# Sheet1.net
KiCad netlist of a schematic drawn in Altium Designer
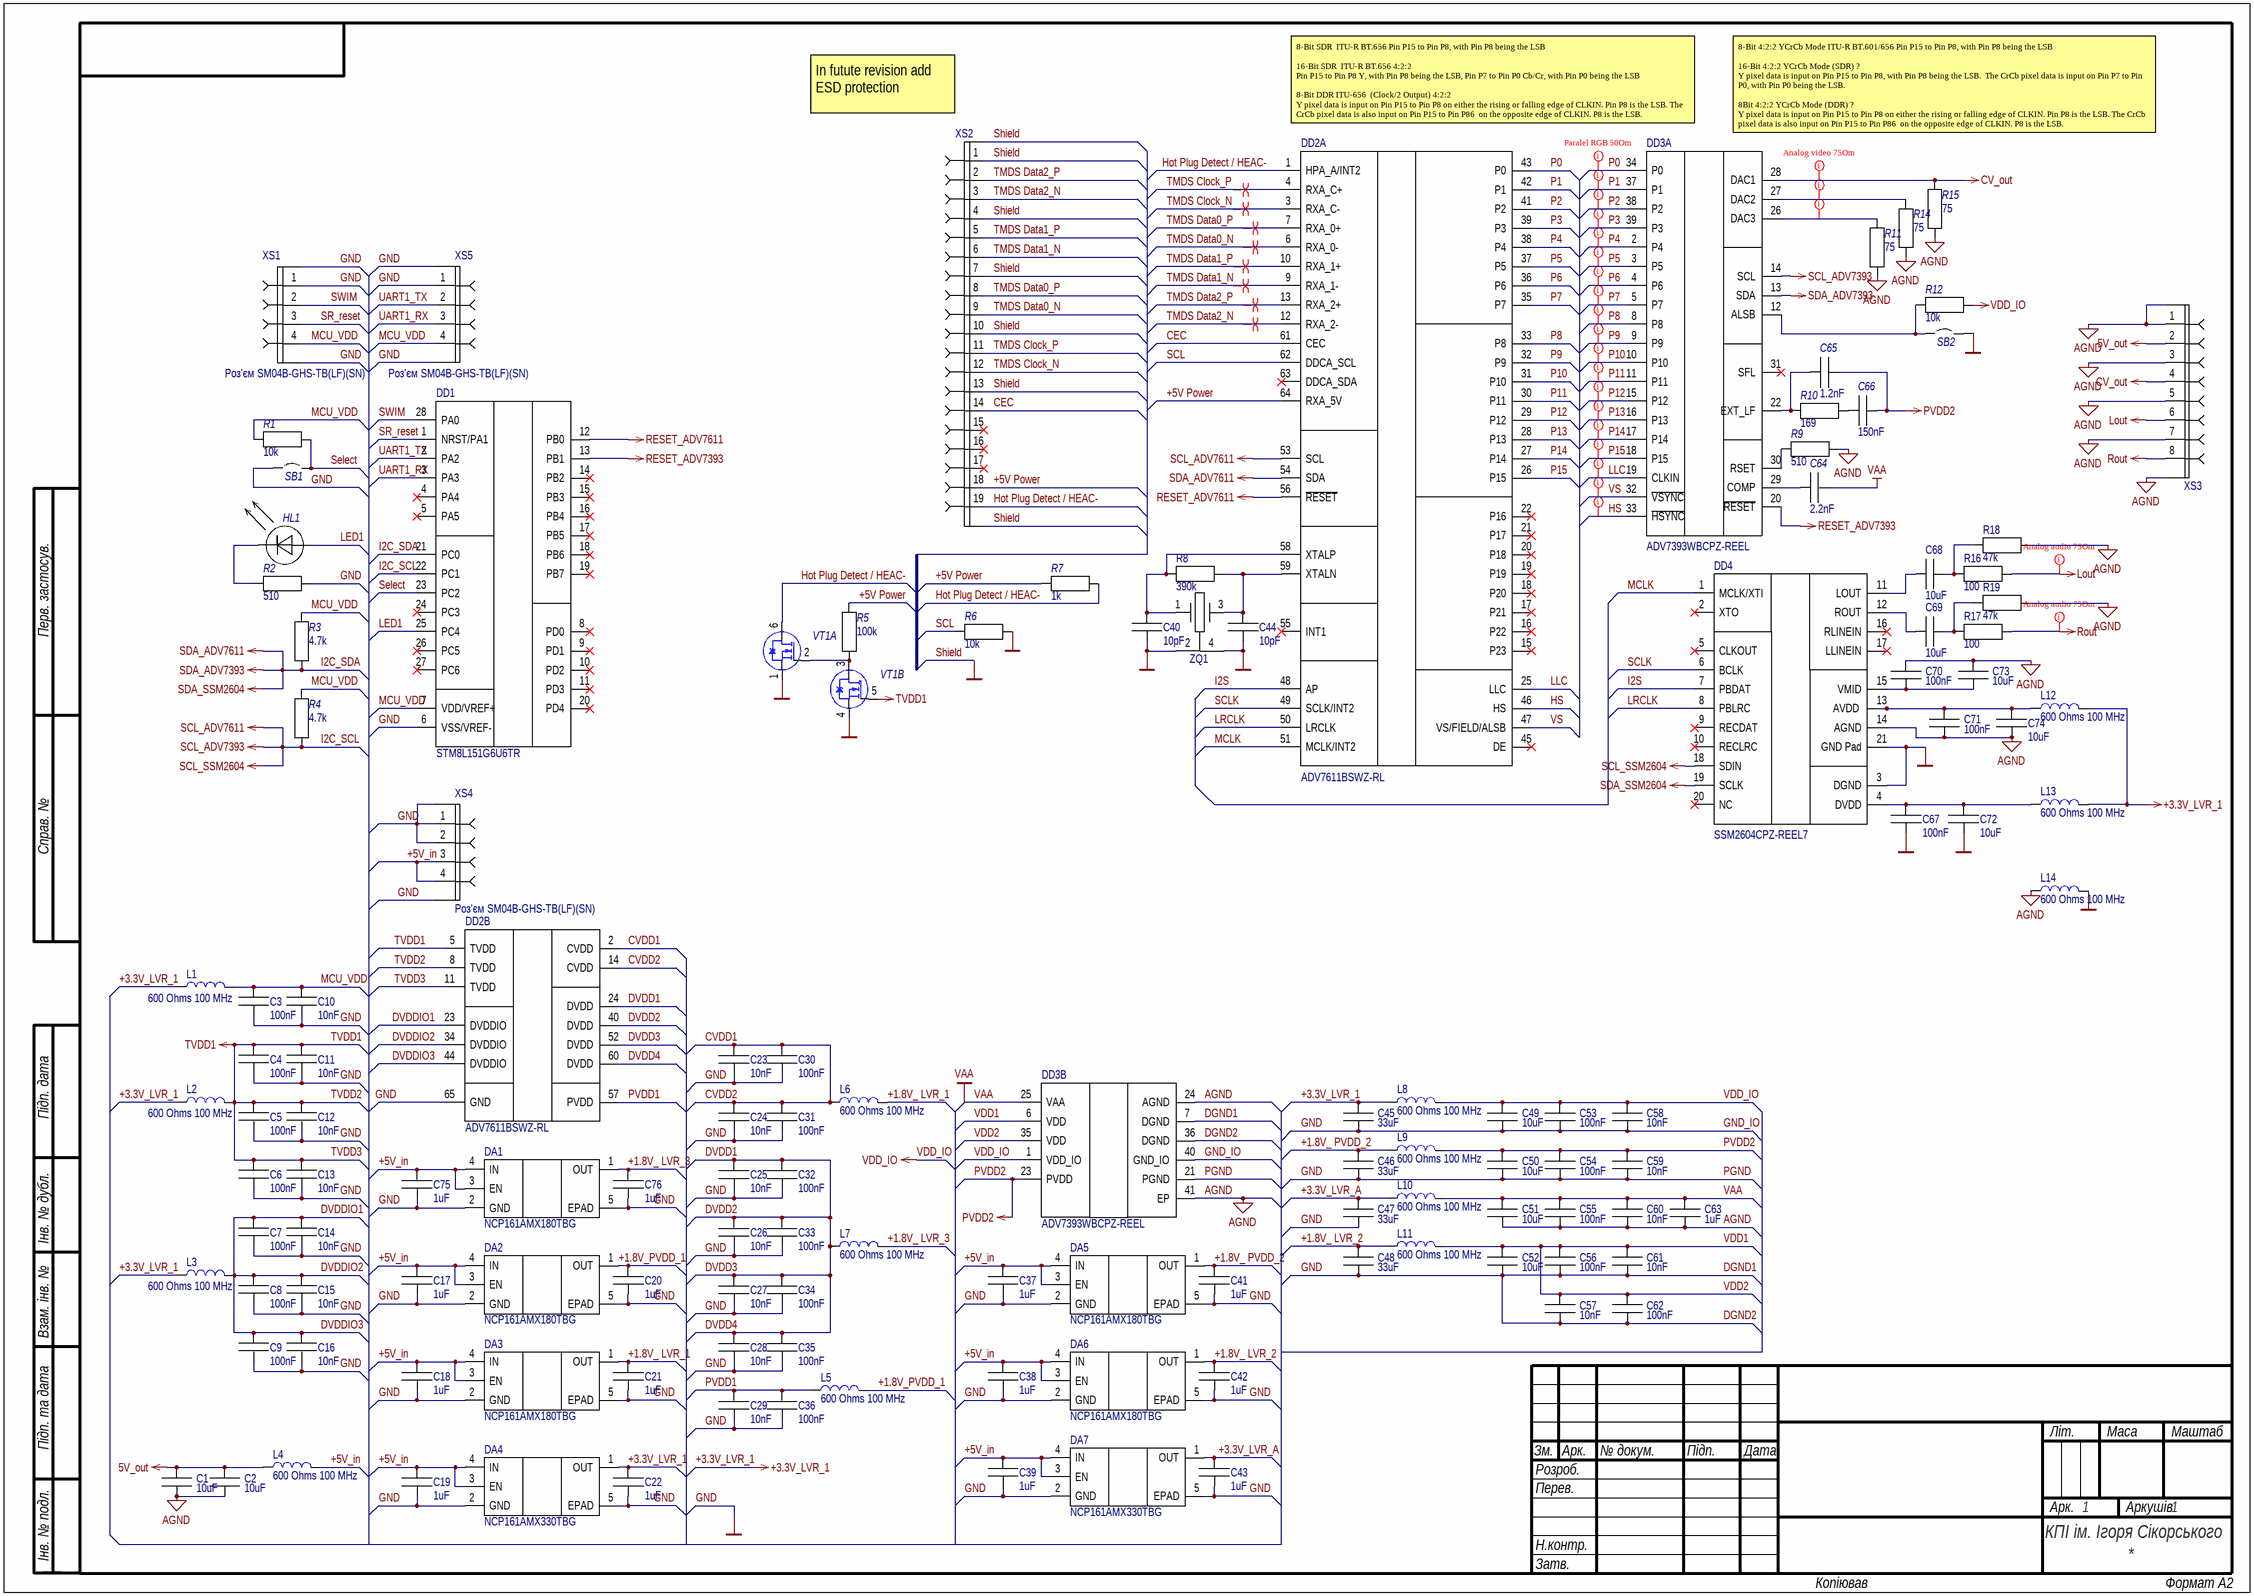
[diagram p0: Sheet1.SchDoc]

(export (version "E")
  (design (tool "Eeschema 10.0.6"))
  (components
    (comp (ref "C1")
      (value "10uF")
      (footprint "SC0603_L")
      (description "10 µF ±20% 6.3V Ceramic Capacitor X5R 0603 (1608 Metric)")
      (fields (field (name "Comment") "CL10A106MQ8NNNC"))
      (libsource (lib "Schlib2") (part "C0603-10µF-6.3V-10CL10A106MQ8NNNC"))
    )
    (comp (ref "C2")
      (value "10uF")
      (footprint "SC0603_L")
      (description "10 µF ±20% 6.3V Ceramic Capacitor X5R 0603 (1608 Metric)")
      (fields (field (name "Comment") "CL10A106MQ8NNNC"))
      (libsource (lib "Schlib2") (part "C0603-10µF-6.3V-10CL10A106MQ8NNNC"))
    )
    (comp (ref "C3")
      (value "100nF")
      (footprint "FP-C0402-BB-IPC_A")
      (description "0.1 µF ±10% 16V Ceramic Capacitor X7R 0402 (1005 Metric)")
      (fields (field (name "Comment") "C0402C104K4RAC7867"))
      (libsource (lib "Schlib2") (part "C0402-100nF-16V-C0402C104K4RAC7867"))
    )
    (comp (ref "C4")
      (value "100nF")
      (footprint "FP-C0402-BB-IPC_A")
      (description "0.1 µF ±10% 16V Ceramic Capacitor X7R 0402 (1005 Metric)")
      (fields (field (name "Comment") "C0402C104K4RAC7867"))
      (libsource (lib "Schlib2") (part "C0402-100nF-16V-C0402C104K4RAC7867"))
    )
    (comp (ref "C5")
      (value "100nF")
      (footprint "FP-C0402-BB-IPC_A")
      (description "0.1 µF ±10% 16V Ceramic Capacitor X7R 0402 (1005 Metric)")
      (fields (field (name "Comment") "C0402C104K4RAC7867"))
      (libsource (lib "Schlib2") (part "C0402-100nF-16V-C0402C104K4RAC7867"))
    )
    (comp (ref "C6")
      (value "100nF")
      (footprint "FP-C0402-BB-IPC_A")
      (description "0.1 µF ±10% 16V Ceramic Capacitor X7R 0402 (1005 Metric)")
      (fields (field (name "Comment") "C0402C104K4RAC7867"))
      (libsource (lib "Schlib2") (part "C0402-100nF-16V-C0402C104K4RAC7867"))
    )
    (comp (ref "C7")
      (value "100nF")
      (footprint "FP-C0402-BB-IPC_A")
      (description "0.1 µF ±10% 16V Ceramic Capacitor X7R 0402 (1005 Metric)")
      (fields (field (name "Comment") "C0402C104K4RAC7867"))
      (libsource (lib "Schlib2") (part "C0402-100nF-16V-C0402C104K4RAC7867"))
    )
    (comp (ref "C8")
      (value "100nF")
      (footprint "FP-C0402-BB-IPC_A")
      (description "0.1 µF ±10% 16V Ceramic Capacitor X7R 0402 (1005 Metric)")
      (fields (field (name "Comment") "C0402C104K4RAC7867"))
      (libsource (lib "Schlib2") (part "C0402-100nF-16V-C0402C104K4RAC7867"))
    )
    (comp (ref "C9")
      (value "100nF")
      (footprint "FP-C0402-BB-IPC_A")
      (description "0.1 µF ±10% 16V Ceramic Capacitor X7R 0402 (1005 Metric)")
      (fields (field (name "Comment") "C0402C104K4RAC7867"))
      (libsource (lib "Schlib2") (part "C0402-100nF-16V-C0402C104K4RAC7867"))
    )
    (comp (ref "C10")
      (value "10nF")
      (footprint "FP-C0402-BB-IPC_A")
      (description "10000 pF ±10% 16V Ceramic Capacitor X7R 0402 (1005 Metric)")
      (fields (field (name "Comment") "C0402C103K4RAC7867"))
      (libsource (lib "Schlib2") (part "C0402-10nF-16V-C0402C103K4RAC7867"))
    )
    (comp (ref "C11")
      (value "10nF")
      (footprint "FP-C0402-BB-IPC_A")
      (description "10000 pF ±10% 16V Ceramic Capacitor X7R 0402 (1005 Metric)")
      (fields (field (name "Comment") "C0402C103K4RAC7867"))
      (libsource (lib "Schlib2") (part "C0402-10nF-16V-C0402C103K4RAC7867"))
    )
    (comp (ref "C12")
      (value "10nF")
      (footprint "FP-C0402-BB-IPC_A")
      (description "10000 pF ±10% 16V Ceramic Capacitor X7R 0402 (1005 Metric)")
      (fields (field (name "Comment") "C0402C103K4RAC7867"))
      (libsource (lib "Schlib2") (part "C0402-10nF-16V-C0402C103K4RAC7867"))
    )
    (comp (ref "C13")
      (value "10nF")
      (footprint "FP-C0402-BB-IPC_A")
      (description "10000 pF ±10% 16V Ceramic Capacitor X7R 0402 (1005 Metric)")
      (fields (field (name "Comment") "C0402C103K4RAC7867"))
      (libsource (lib "Schlib2") (part "C0402-10nF-16V-C0402C103K4RAC7867"))
    )
    (comp (ref "C14")
      (value "10nF")
      (footprint "FP-C0402-BB-IPC_A")
      (description "10000 pF ±10% 16V Ceramic Capacitor X7R 0402 (1005 Metric)")
      (fields (field (name "Comment") "C0402C103K4RAC7867"))
      (libsource (lib "Schlib2") (part "C0402-10nF-16V-C0402C103K4RAC7867"))
    )
    (comp (ref "C15")
      (value "10nF")
      (footprint "FP-C0402-BB-IPC_A")
      (description "10000 pF ±10% 16V Ceramic Capacitor X7R 0402 (1005 Metric)")
      (fields (field (name "Comment") "C0402C103K4RAC7867"))
      (libsource (lib "Schlib2") (part "C0402-10nF-16V-C0402C103K4RAC7867"))
    )
    (comp (ref "C16")
      (value "10nF")
      (footprint "FP-C0402-BB-IPC_A")
      (description "10000 pF ±10% 16V Ceramic Capacitor X7R 0402 (1005 Metric)")
      (fields (field (name "Comment") "C0402C103K4RAC7867"))
      (libsource (lib "Schlib2") (part "C0402-10nF-16V-C0402C103K4RAC7867"))
    )
    (comp (ref "C17")
      (value "1uF")
      (footprint "SC0603_L")
      (description "1 µF ±10% 25V Ceramic Capacitor X5R 0603 (1608 Metric)")
      (fields (field (name "Comment") "CC0603KRX5R8BB105"))
      (libsource (lib "Schlib2") (part "C0603-1µF-25V-CC0603KRX5R8BB105"))
    )
    (comp (ref "C18")
      (value "1uF")
      (footprint "SC0603_L")
      (description "1 µF ±10% 25V Ceramic Capacitor X5R 0603 (1608 Metric)")
      (fields (field (name "Comment") "CC0603KRX5R8BB105"))
      (libsource (lib "Schlib2") (part "C0603-1µF-25V-CC0603KRX5R8BB105"))
    )
    (comp (ref "C19")
      (value "1uF")
      (footprint "SC0603_L")
      (description "1 µF ±10% 25V Ceramic Capacitor X5R 0603 (1608 Metric)")
      (fields (field (name "Comment") "CC0603KRX5R8BB105"))
      (libsource (lib "Schlib2") (part "C0603-1µF-25V-CC0603KRX5R8BB105"))
    )
    (comp (ref "C20")
      (value "1uF")
      (footprint "SC0603_L")
      (description "1 µF ±10% 25V Ceramic Capacitor X5R 0603 (1608 Metric)")
      (fields (field (name "Comment") "CC0603KRX5R8BB105"))
      (libsource (lib "Schlib2") (part "C0603-1µF-25V-CC0603KRX5R8BB105"))
    )
    (comp (ref "C21")
      (value "1uF")
      (footprint "SC0603_L")
      (description "1 µF ±10% 25V Ceramic Capacitor X5R 0603 (1608 Metric)")
      (fields (field (name "Comment") "CC0603KRX5R8BB105"))
      (libsource (lib "Schlib2") (part "C0603-1µF-25V-CC0603KRX5R8BB105"))
    )
    (comp (ref "C22")
      (value "1uF")
      (footprint "SC0603_L")
      (description "1 µF ±10% 25V Ceramic Capacitor X5R 0603 (1608 Metric)")
      (fields (field (name "Comment") "CC0603KRX5R8BB105"))
      (libsource (lib "Schlib2") (part "C0603-1µF-25V-CC0603KRX5R8BB105"))
    )
    (comp (ref "C23")
      (value "10nF")
      (footprint "FP-C0402-BB-IPC_A")
      (description "10000 pF ±10% 16V Ceramic Capacitor X7R 0402 (1005 Metric)")
      (fields (field (name "Comment") "C0402C103K4RAC7867"))
      (libsource (lib "Schlib2") (part "C0402-10nF-16V-C0402C103K4RAC7867"))
    )
    (comp (ref "C24")
      (value "10nF")
      (footprint "FP-C0402-BB-IPC_A")
      (description "10000 pF ±10% 16V Ceramic Capacitor X7R 0402 (1005 Metric)")
      (fields (field (name "Comment") "C0402C103K4RAC7867"))
      (libsource (lib "Schlib2") (part "C0402-10nF-16V-C0402C103K4RAC7867"))
    )
    (comp (ref "C25")
      (value "10nF")
      (footprint "FP-C0402-BB-IPC_A")
      (description "10000 pF ±10% 16V Ceramic Capacitor X7R 0402 (1005 Metric)")
      (fields (field (name "Comment") "C0402C103K4RAC7867"))
      (libsource (lib "Schlib2") (part "C0402-10nF-16V-C0402C103K4RAC7867"))
    )
    (comp (ref "C26")
      (value "10nF")
      (footprint "FP-C0402-BB-IPC_A")
      (description "10000 pF ±10% 16V Ceramic Capacitor X7R 0402 (1005 Metric)")
      (fields (field (name "Comment") "C0402C103K4RAC7867"))
      (libsource (lib "Schlib2") (part "C0402-10nF-16V-C0402C103K4RAC7867"))
    )
    (comp (ref "C27")
      (value "10nF")
      (footprint "FP-C0402-BB-IPC_A")
      (description "10000 pF ±10% 16V Ceramic Capacitor X7R 0402 (1005 Metric)")
      (fields (field (name "Comment") "C0402C103K4RAC7867"))
      (libsource (lib "Schlib2") (part "C0402-10nF-16V-C0402C103K4RAC7867"))
    )
    (comp (ref "C28")
      (value "10nF")
      (footprint "FP-C0402-BB-IPC_A")
      (description "10000 pF ±10% 16V Ceramic Capacitor X7R 0402 (1005 Metric)")
      (fields (field (name "Comment") "C0402C103K4RAC7867"))
      (libsource (lib "Schlib2") (part "C0402-10nF-16V-C0402C103K4RAC7867"))
    )
    (comp (ref "C29")
      (value "10nF")
      (footprint "FP-C0402-BB-IPC_A")
      (description "10000 pF ±10% 16V Ceramic Capacitor X7R 0402 (1005 Metric)")
      (fields (field (name "Comment") "C0402C103K4RAC7867"))
      (libsource (lib "Schlib2") (part "C0402-10nF-16V-C0402C103K4RAC7867"))
    )
    (comp (ref "C30")
      (value "100nF")
      (footprint "FP-C0402-BB-IPC_A")
      (description "0.1 µF ±10% 16V Ceramic Capacitor X7R 0402 (1005 Metric)")
      (fields (field (name "Comment") "C0402C104K4RAC7867"))
      (libsource (lib "Schlib2") (part "C0402-100nF-16V-C0402C104K4RAC7867"))
    )
    (comp (ref "C31")
      (value "100nF")
      (footprint "FP-C0402-BB-IPC_A")
      (description "0.1 µF ±10% 16V Ceramic Capacitor X7R 0402 (1005 Metric)")
      (fields (field (name "Comment") "C0402C104K4RAC7867"))
      (libsource (lib "Schlib2") (part "C0402-100nF-16V-C0402C104K4RAC7867"))
    )
    (comp (ref "C32")
      (value "100nF")
      (footprint "FP-C0402-BB-IPC_A")
      (description "0.1 µF ±10% 16V Ceramic Capacitor X7R 0402 (1005 Metric)")
      (fields (field (name "Comment") "C0402C104K4RAC7867"))
      (libsource (lib "Schlib2") (part "C0402-100nF-16V-C0402C104K4RAC7867"))
    )
    (comp (ref "C33")
      (value "100nF")
      (footprint "FP-C0402-BB-IPC_A")
      (description "0.1 µF ±10% 16V Ceramic Capacitor X7R 0402 (1005 Metric)")
      (fields (field (name "Comment") "C0402C104K4RAC7867"))
      (libsource (lib "Schlib2") (part "C0402-100nF-16V-C0402C104K4RAC7867"))
    )
    (comp (ref "C34")
      (value "100nF")
      (footprint "FP-C0402-BB-IPC_A")
      (description "0.1 µF ±10% 16V Ceramic Capacitor X7R 0402 (1005 Metric)")
      (fields (field (name "Comment") "C0402C104K4RAC7867"))
      (libsource (lib "Schlib2") (part "C0402-100nF-16V-C0402C104K4RAC7867"))
    )
    (comp (ref "C35")
      (value "100nF")
      (footprint "FP-C0402-BB-IPC_A")
      (description "0.1 µF ±10% 16V Ceramic Capacitor X7R 0402 (1005 Metric)")
      (fields (field (name "Comment") "C0402C104K4RAC7867"))
      (libsource (lib "Schlib2") (part "C0402-100nF-16V-C0402C104K4RAC7867"))
    )
    (comp (ref "C36")
      (value "100nF")
      (footprint "FP-C0402-BB-IPC_A")
      (description "0.1 µF ±10% 16V Ceramic Capacitor X7R 0402 (1005 Metric)")
      (fields (field (name "Comment") "C0402C104K4RAC7867"))
      (libsource (lib "Schlib2") (part "C0402-100nF-16V-C0402C104K4RAC7867"))
    )
    (comp (ref "C37")
      (value "1uF")
      (footprint "SC0603_L")
      (description "1 µF ±10% 25V Ceramic Capacitor X5R 0603 (1608 Metric)")
      (fields (field (name "Comment") "CC0603KRX5R8BB105"))
      (libsource (lib "Schlib2") (part "C0603-1µF-25V-CC0603KRX5R8BB105"))
    )
    (comp (ref "C38")
      (value "1uF")
      (footprint "SC0603_L")
      (description "1 µF ±10% 25V Ceramic Capacitor X5R 0603 (1608 Metric)")
      (fields (field (name "Comment") "CC0603KRX5R8BB105"))
      (libsource (lib "Schlib2") (part "C0603-1µF-25V-CC0603KRX5R8BB105"))
    )
    (comp (ref "C39")
      (value "1uF")
      (footprint "SC0603_L")
      (description "1 µF ±10% 25V Ceramic Capacitor X5R 0603 (1608 Metric)")
      (fields (field (name "Comment") "CC0603KRX5R8BB105"))
      (libsource (lib "Schlib2") (part "C0603-1µF-25V-CC0603KRX5R8BB105"))
    )
    (comp (ref "C40")
      (value "10pF")
      (footprint "SC0603_L")
      (description "10 pF ±1% 16V Ceramic Capacitor X8R 0603 (1608 Metric)")
      (fields (field (name "Comment") "C0603-10pF-16V-C0603C100F4HAC7867"))
      (libsource (lib "Schlib2") (part "C0603-10pF-16V-C0603C100F4HAC7867"))
    )
    (comp (ref "C41")
      (value "1uF")
      (footprint "SC0603_L")
      (description "1 µF ±10% 25V Ceramic Capacitor X5R 0603 (1608 Metric)")
      (fields (field (name "Comment") "CC0603KRX5R8BB105"))
      (libsource (lib "Schlib2") (part "C0603-1µF-25V-CC0603KRX5R8BB105"))
    )
    (comp (ref "C42")
      (value "1uF")
      (footprint "SC0603_L")
      (description "1 µF ±10% 25V Ceramic Capacitor X5R 0603 (1608 Metric)")
      (fields (field (name "Comment") "CC0603KRX5R8BB105"))
      (libsource (lib "Schlib2") (part "C0603-1µF-25V-CC0603KRX5R8BB105"))
    )
    (comp (ref "C43")
      (value "1uF")
      (footprint "SC0603_L")
      (description "1 µF ±10% 25V Ceramic Capacitor X5R 0603 (1608 Metric)")
      (fields (field (name "Comment") "CC0603KRX5R8BB105"))
      (libsource (lib "Schlib2") (part "C0603-1µF-25V-CC0603KRX5R8BB105"))
    )
    (comp (ref "C44")
      (value "10pF")
      (footprint "SC0603_L")
      (description "10 pF ±1% 16V Ceramic Capacitor X8R 0603 (1608 Metric)")
      (fields (field (name "Comment") "C0603-10pF-16V-C0603C100F4HAC7867"))
      (libsource (lib "Schlib2") (part "C0603-10pF-16V-C0603C100F4HAC7867"))
    )
    (comp (ref "C45")
      (value "33uF")
      (footprint "1206")
      (description "33 µF ±20% 25V Ceramic Capacitor X5R 1206 (3216 Metric)")
      (fields (field (name "Comment") "C3216X5R1E336M160AC"))
      (libsource (lib "Schlib2") (part "C1206_33uF_25V_C3216X5R1E336M160AC"))
    )
    (comp (ref "C46")
      (value "33uF")
      (footprint "1206")
      (description "33 µF ±20% 25V Ceramic Capacitor X5R 1206 (3216 Metric)")
      (fields (field (name "Comment") "C3216X5R1E336M160AC"))
      (libsource (lib "Schlib2") (part "C1206_33uF_25V_C3216X5R1E336M160AC"))
    )
    (comp (ref "C47")
      (value "33uF")
      (footprint "1206")
      (description "33 µF ±20% 25V Ceramic Capacitor X5R 1206 (3216 Metric)")
      (fields (field (name "Comment") "C3216X5R1E336M160AC"))
      (libsource (lib "Schlib2") (part "C1206_33uF_25V_C3216X5R1E336M160AC"))
    )
    (comp (ref "C48")
      (value "33uF")
      (footprint "1206")
      (description "33 µF ±20% 25V Ceramic Capacitor X5R 1206 (3216 Metric)")
      (fields (field (name "Comment") "C3216X5R1E336M160AC"))
      (libsource (lib "Schlib2") (part "C1206_33uF_25V_C3216X5R1E336M160AC"))
    )
    (comp (ref "C49")
      (value "10uF")
      (footprint "SC0603_L")
      (description "10 µF ±20% 6.3V Ceramic Capacitor X5R 0603 (1608 Metric)")
      (fields (field (name "Comment") "CL10A106MQ8NNNC"))
      (libsource (lib "Schlib2") (part "C0603-10µF-6.3V-10CL10A106MQ8NNNC"))
    )
    (comp (ref "C50")
      (value "10uF")
      (footprint "SC0603_L")
      (description "10 µF ±20% 6.3V Ceramic Capacitor X5R 0603 (1608 Metric)")
      (fields (field (name "Comment") "CL10A106MQ8NNNC"))
      (libsource (lib "Schlib2") (part "C0603-10µF-6.3V-10CL10A106MQ8NNNC"))
    )
    (comp (ref "C51")
      (value "10uF")
      (footprint "SC0603_L")
      (description "10 µF ±20% 6.3V Ceramic Capacitor X5R 0603 (1608 Metric)")
      (fields (field (name "Comment") "CL10A106MQ8NNNC"))
      (libsource (lib "Schlib2") (part "C0603-10µF-6.3V-10CL10A106MQ8NNNC"))
    )
    (comp (ref "C52")
      (value "10uF")
      (footprint "SC0603_L")
      (description "10 µF ±20% 6.3V Ceramic Capacitor X5R 0603 (1608 Metric)")
      (fields (field (name "Comment") "CL10A106MQ8NNNC"))
      (libsource (lib "Schlib2") (part "C0603-10µF-6.3V-10CL10A106MQ8NNNC"))
    )
    (comp (ref "C53")
      (value "100nF")
      (footprint "FP-C0402-BB-IPC_A")
      (description "0.1 µF ±10% 16V Ceramic Capacitor X7R 0402 (1005 Metric)")
      (fields (field (name "Comment") "C0402C104K4RAC7867"))
      (libsource (lib "Schlib2") (part "C0402-100nF-16V-C0402C104K4RAC7867"))
    )
    (comp (ref "C54")
      (value "100nF")
      (footprint "FP-C0402-BB-IPC_A")
      (description "0.1 µF ±10% 16V Ceramic Capacitor X7R 0402 (1005 Metric)")
      (fields (field (name "Comment") "C0402C104K4RAC7867"))
      (libsource (lib "Schlib2") (part "C0402-100nF-16V-C0402C104K4RAC7867"))
    )
    (comp (ref "C55")
      (value "100nF")
      (footprint "FP-C0402-BB-IPC_A")
      (description "0.1 µF ±10% 16V Ceramic Capacitor X7R 0402 (1005 Metric)")
      (fields (field (name "Comment") "C0402C104K4RAC7867"))
      (libsource (lib "Schlib2") (part "C0402-100nF-16V-C0402C104K4RAC7867"))
    )
    (comp (ref "C56")
      (value "100nF")
      (footprint "FP-C0402-BB-IPC_A")
      (description "0.1 µF ±10% 16V Ceramic Capacitor X7R 0402 (1005 Metric)")
      (fields (field (name "Comment") "C0402C104K4RAC7867"))
      (libsource (lib "Schlib2") (part "C0402-100nF-16V-C0402C104K4RAC7867"))
    )
    (comp (ref "C57")
      (value "10nF")
      (footprint "FP-C0402-BB-IPC_A")
      (description "10000 pF ±10% 16V Ceramic Capacitor X7R 0402 (1005 Metric)")
      (fields (field (name "Comment") "C0402C103K4RAC7867"))
      (libsource (lib "Schlib2") (part "C0402-10nF-16V-C0402C103K4RAC7867"))
    )
    (comp (ref "C58")
      (value "10nF")
      (footprint "FP-C0402-BB-IPC_A")
      (description "10000 pF ±10% 16V Ceramic Capacitor X7R 0402 (1005 Metric)")
      (fields (field (name "Comment") "C0402C103K4RAC7867"))
      (libsource (lib "Schlib2") (part "C0402-10nF-16V-C0402C103K4RAC7867"))
    )
    (comp (ref "C59")
      (value "10nF")
      (footprint "FP-C0402-BB-IPC_A")
      (description "10000 pF ±10% 16V Ceramic Capacitor X7R 0402 (1005 Metric)")
      (fields (field (name "Comment") "C0402C103K4RAC7867"))
      (libsource (lib "Schlib2") (part "C0402-10nF-16V-C0402C103K4RAC7867"))
    )
    (comp (ref "C60")
      (value "10nF")
      (footprint "FP-C0402-BB-IPC_A")
      (description "10000 pF ±10% 16V Ceramic Capacitor X7R 0402 (1005 Metric)")
      (fields (field (name "Comment") "C0402C103K4RAC7867"))
      (libsource (lib "Schlib2") (part "C0402-10nF-16V-C0402C103K4RAC7867"))
    )
    (comp (ref "C61")
      (value "10nF")
      (footprint "FP-C0402-BB-IPC_A")
      (description "10000 pF ±10% 16V Ceramic Capacitor X7R 0402 (1005 Metric)")
      (fields (field (name "Comment") "C0402C103K4RAC7867"))
      (libsource (lib "Schlib2") (part "C0402-10nF-16V-C0402C103K4RAC7867"))
    )
    (comp (ref "C62")
      (value "100nF")
      (footprint "FP-C0402-BB-IPC_A")
      (description "0.1 µF ±10% 16V Ceramic Capacitor X7R 0402 (1005 Metric)")
      (fields (field (name "Comment") "C0402C104K4RAC7867"))
      (libsource (lib "Schlib2") (part "C0402-100nF-16V-C0402C104K4RAC7867"))
    )
    (comp (ref "C63")
      (value "1uF")
      (footprint "SC0603_L")
      (description "1 µF ±10% 25V Ceramic Capacitor X5R 0603 (1608 Metric)")
      (fields (field (name "Comment") "CC0603KRX5R8BB105"))
      (libsource (lib "Schlib2") (part "C0603-1µF-25V-CC0603KRX5R8BB105"))
    )
    (comp (ref "C64")
      (value "2.2nF")
      (footprint "FP-C0402-BB-IPC_A")
      (description "2200 pF ±10% 25V Ceramic Capacitor X7R 0402 (1005 Metric)")
      (fields (field (name "Comment") "C0402C222K3RAC7867"))
      (libsource (lib "Schlib2") (part "C0402-2.2nF-25V-C0402C222K3RAC7867"))
    )
    (comp (ref "C65")
      (value "1.2nF")
      (footprint "FP-C0402-BB-IPC_A")
      (description "1200 pF ±5% 50V Ceramic Capacitor C0G, NP0 0402 (1005 Metric)")
      (fields (field (name "Comment") "C0402C222K3RAC7867"))
      (libsource (lib "Schlib2") (part "C0402-1.2nF-50V-C0402C122J5GAC7867"))
    )
    (comp (ref "C66")
      (value "150nF")
      (footprint "FP-C0402-BB-IPC_A")
      (description "0.15 µF ±10% 35V Ceramic Capacitor X7R 0402 (1005 Metric)")
      (fields (field (name "Comment") "CGA2B1X7R1V154K050BC"))
      (libsource (lib "Schlib2") (part "C0402-150nF-35V-CGA2B1X7R1V154K050BC"))
    )
    (comp (ref "C67")
      (value "100nF")
      (footprint "FP-C0402-BB-IPC_A")
      (description "0.1 µF ±10% 16V Ceramic Capacitor X7R 0402 (1005 Metric)")
      (fields (field (name "Comment") "C0402C104K4RAC7867"))
      (libsource (lib "Schlib2") (part "C0402-100nF-16V-C0402C104K4RAC7867"))
    )
    (comp (ref "C68")
      (value "10uF")
      (footprint "SC0603_L")
      (description "10 µF ±20% 6.3V Ceramic Capacitor X5R 0603 (1608 Metric)")
      (fields (field (name "Comment") "CL10A106MQ8NNNC"))
      (libsource (lib "Schlib2") (part "C0603-10µF-6.3V-10CL10A106MQ8NNNC"))
    )
    (comp (ref "C69")
      (value "10uF")
      (footprint "SC0603_L")
      (description "10 µF ±20% 6.3V Ceramic Capacitor X5R 0603 (1608 Metric)")
      (fields (field (name "Comment") "CL10A106MQ8NNNC"))
      (libsource (lib "Schlib2") (part "C0603-10µF-6.3V-10CL10A106MQ8NNNC"))
    )
    (comp (ref "C70")
      (value "100nF")
      (footprint "FP-C0402-BB-IPC_A")
      (description "0.1 µF ±10% 16V Ceramic Capacitor X7R 0402 (1005 Metric)")
      (fields (field (name "Comment") "C0402C104K4RAC7867"))
      (libsource (lib "Schlib2") (part "C0402-100nF-16V-C0402C104K4RAC7867"))
    )
    (comp (ref "C71")
      (value "100nF")
      (footprint "FP-C0402-BB-IPC_A")
      (description "0.1 µF ±10% 16V Ceramic Capacitor X7R 0402 (1005 Metric)")
      (fields (field (name "Comment") "C0402C104K4RAC7867"))
      (libsource (lib "Schlib2") (part "C0402-100nF-16V-C0402C104K4RAC7867"))
    )
    (comp (ref "C72")
      (value "10uF")
      (footprint "SC0603_L")
      (description "10 µF ±20% 6.3V Ceramic Capacitor X5R 0603 (1608 Metric)")
      (fields (field (name "Comment") "CL10A106MQ8NNNC"))
      (libsource (lib "Schlib2") (part "C0603-10µF-6.3V-10CL10A106MQ8NNNC"))
    )
    (comp (ref "C73")
      (value "10uF")
      (footprint "SC0603_L")
      (description "10 µF ±20% 6.3V Ceramic Capacitor X5R 0603 (1608 Metric)")
      (fields (field (name "Comment") "CL10A106MQ8NNNC"))
      (libsource (lib "Schlib2") (part "C0603-10µF-6.3V-10CL10A106MQ8NNNC"))
    )
    (comp (ref "C74")
      (value "10uF")
      (footprint "SC0603_L")
      (description "10 µF ±20% 6.3V Ceramic Capacitor X5R 0603 (1608 Metric)")
      (fields (field (name "Comment") "CL10A106MQ8NNNC"))
      (libsource (lib "Schlib2") (part "C0603-10µF-6.3V-10CL10A106MQ8NNNC"))
    )
    (comp (ref "C75")
      (value "1uF")
      (footprint "SC0603_L")
      (description "1 µF ±10% 25V Ceramic Capacitor X5R 0603 (1608 Metric)")
      (fields (field (name "Comment") "CC0603KRX5R8BB105"))
      (libsource (lib "Schlib2") (part "C0603-1µF-25V-CC0603KRX5R8BB105"))
    )
    (comp (ref "C76")
      (value "1uF")
      (footprint "SC0603_L")
      (description "1 µF ±10% 25V Ceramic Capacitor X5R 0603 (1608 Metric)")
      (fields (field (name "Comment") "CC0603KRX5R8BB105"))
      (libsource (lib "Schlib2") (part "C0603-1µF-25V-CC0603KRX5R8BB105"))
    )
    (comp (ref "DA1")
      (value "NCP161AMX180TBG")
      (footprint "XDFN4_711AJ_ONS_OSI")
      (description "IC REG LINEAR 1.8V 450MA 4XDFN")
      (libsource (lib "Schlib2") (part "NCP161AMX180TBG"))
    )
    (comp (ref "DA2")
      (value "NCP161AMX180TBG")
      (footprint "XDFN4_711AJ_ONS_OSI")
      (description "IC REG LINEAR 1.8V 450MA 4XDFN")
      (libsource (lib "Schlib2") (part "NCP161AMX180TBG"))
    )
    (comp (ref "DA3")
      (value "NCP161AMX180TBG")
      (footprint "XDFN4_711AJ_ONS_OSI")
      (description "IC REG LINEAR 1.8V 450MA 4XDFN")
      (libsource (lib "Schlib2") (part "NCP161AMX180TBG"))
    )
    (comp (ref "DA4")
      (value "NCP161AMX330TBG")
      (footprint "XDFN4_711AJ_ONS_OSI")
      (description "IC REG LINEAR 3.3V 450MA 4XDFN")
      (libsource (lib "Schlib2") (part "NCP161AMX330TBG"))
    )
    (comp (ref "DA5")
      (value "NCP161AMX180TBG")
      (footprint "XDFN4_711AJ_ONS_OSI")
      (description "IC REG LINEAR 1.8V 450MA 4XDFN")
      (libsource (lib "Schlib2") (part "NCP161AMX180TBG"))
    )
    (comp (ref "DA6")
      (value "NCP161AMX180TBG")
      (footprint "XDFN4_711AJ_ONS_OSI")
      (description "IC REG LINEAR 1.8V 450MA 4XDFN")
      (libsource (lib "Schlib2") (part "NCP161AMX180TBG"))
    )
    (comp (ref "DA7")
      (value "NCP161AMX330TBG")
      (footprint "XDFN4_711AJ_ONS_OSI")
      (description "IC REG LINEAR 3.3V 450MA 4XDFN")
      (libsource (lib "Schlib2") (part "NCP161AMX330TBG"))
    )
    (comp (ref "DD1")
      (value "STM8L151G6U6TR")
      (footprint "UFQFPN28-4x4mm")
      (description "STM8 STM8L EnergyLite Microcontroller IC 8-Bit 16MHz 32KB (32K x 8) FLASH 28-UFQFPN (4x4)")
      (libsource (lib "Schlib2") (part "STM8L151G6U6TR"))
    )
    (comp (ref "DD2")
      (value "ADV7611BSWZ-RL")
      (footprint "ADI-SW-64-2_N")
      (description "Video Receiver IC I2C, I2S HDMI 1.4a, IEC 60958 64-LQFP-EP (10x10) Package")
      (libsource (lib "Schlib2") (part "ADV7611BSWZ-RL"))
    )
    (comp (ref "DD3")
      (value "ADV7393WBCPZ-REEL")
      (footprint "ADI-CP-40-1_N")
      (libsource (lib "Schlib2") (part "ADV7393WBCPZ-REEL"))
    )
    (comp (ref "DD4")
      (value "SSM2604CPZ-REEL7")
      (footprint "CP_20_4_ADI")
      (description "Stereo Audio Interface 24 b Serial 20-LFCSP (4x4)")
      (libsource (lib "Schlib2") (part "SSM2604CPZ-REEL7"))
    )
    (comp (ref "HL1")
      (value "LTST-C170GKT")
      (footprint "LED_0805_G")
      (description "Green 569nm LED Indication - Discrete 2.1V 0805 (2012 Metric)")
      (libsource (lib "Schlib2") (part "LED_0805_LTST-C170GKT"))
    )
    (comp (ref "L1")
      (value "600 Ohms 100 MHz")
      (footprint "SC0603_L")
      (description "600 Ohms @ 100 MHz 1 Ferrite Bead 0603 (1608 Metric) 2A 100mOhm")
      (fields (field (name "Comment") "ferrite bead"))
      (libsource (lib "Schlib2") (part "BBHV00160808601Y00"))
    )
    (comp (ref "L2")
      (value "600 Ohms 100 MHz")
      (footprint "SC0603_L")
      (description "600 Ohms @ 100 MHz 1 Ferrite Bead 0603 (1608 Metric) 2A 100mOhm")
      (fields (field (name "Comment") "ferrite bead"))
      (libsource (lib "Schlib2") (part "BBHV00160808601Y00"))
    )
    (comp (ref "L3")
      (value "600 Ohms 100 MHz")
      (footprint "SC0603_L")
      (description "600 Ohms @ 100 MHz 1 Ferrite Bead 0603 (1608 Metric) 2A 100mOhm")
      (fields (field (name "Comment") "ferrite bead"))
      (libsource (lib "Schlib2") (part "BBHV00160808601Y00"))
    )
    (comp (ref "L4")
      (value "600 Ohms 100 MHz")
      (footprint "SC0603_L")
      (description "600 Ohms @ 100 MHz 1 Ferrite Bead 0603 (1608 Metric) 2A 100mOhm")
      (fields (field (name "Comment") "ferrite bead"))
      (libsource (lib "Schlib2") (part "BBHV00160808601Y00"))
    )
    (comp (ref "L5")
      (value "600 Ohms 100 MHz")
      (footprint "SC0603_L")
      (description "600 Ohms @ 100 MHz 1 Ferrite Bead 0603 (1608 Metric) 2A 100mOhm")
      (fields (field (name "Comment") "ferrite bead"))
      (libsource (lib "Schlib2") (part "BBHV00160808601Y00"))
    )
    (comp (ref "L6")
      (value "600 Ohms 100 MHz")
      (footprint "SC0603_L")
      (description "600 Ohms @ 100 MHz 1 Ferrite Bead 0603 (1608 Metric) 2A 100mOhm")
      (fields (field (name "Comment") "ferrite bead"))
      (libsource (lib "Schlib2") (part "BBHV00160808601Y00"))
    )
    (comp (ref "L7")
      (value "600 Ohms 100 MHz")
      (footprint "SC0603_L")
      (description "600 Ohms @ 100 MHz 1 Ferrite Bead 0603 (1608 Metric) 2A 100mOhm")
      (fields (field (name "Comment") "ferrite bead"))
      (libsource (lib "Schlib2") (part "BBHV00160808601Y00"))
    )
    (comp (ref "L8")
      (value "600 Ohms 100 MHz")
      (footprint "SC0603_L")
      (description "600 Ohms @ 100 MHz 1 Ferrite Bead 0603 (1608 Metric) 2A 100mOhm")
      (fields (field (name "Comment") "ferrite bead"))
      (libsource (lib "Schlib2") (part "BBHV00160808601Y00"))
    )
    (comp (ref "L9")
      (value "600 Ohms 100 MHz")
      (footprint "SC0603_L")
      (description "600 Ohms @ 100 MHz 1 Ferrite Bead 0603 (1608 Metric) 2A 100mOhm")
      (fields (field (name "Comment") "ferrite bead"))
      (libsource (lib "Schlib2") (part "BBHV00160808601Y00"))
    )
    (comp (ref "L10")
      (value "600 Ohms 100 MHz")
      (footprint "SC0603_L")
      (description "600 Ohms @ 100 MHz 1 Ferrite Bead 0603 (1608 Metric) 2A 100mOhm")
      (fields (field (name "Comment") "ferrite bead"))
      (libsource (lib "Schlib2") (part "BBHV00160808601Y00"))
    )
    (comp (ref "L11")
      (value "600 Ohms 100 MHz")
      (footprint "SC0603_L")
      (description "600 Ohms @ 100 MHz 1 Ferrite Bead 0603 (1608 Metric) 2A 100mOhm")
      (fields (field (name "Comment") "ferrite bead"))
      (libsource (lib "Schlib2") (part "BBHV00160808601Y00"))
    )
    (comp (ref "L12")
      (value "600 Ohms 100 MHz")
      (footprint "SC0603_L")
      (description "600 Ohms @ 100 MHz 1 Ferrite Bead 0603 (1608 Metric) 2A 100mOhm")
      (fields (field (name "Comment") "ferrite bead"))
      (libsource (lib "Schlib2") (part "BBHV00160808601Y00"))
    )
    (comp (ref "L13")
      (value "600 Ohms 100 MHz")
      (footprint "SC0603_L")
      (description "600 Ohms @ 100 MHz 1 Ferrite Bead 0603 (1608 Metric) 2A 100mOhm")
      (fields (field (name "Comment") "ferrite bead"))
      (libsource (lib "Schlib2") (part "BBHV00160808601Y00"))
    )
    (comp (ref "L14")
      (value "600 Ohms 100 MHz")
      (footprint "SC0603_L")
      (description "600 Ohms @ 100 MHz 1 Ferrite Bead 0603 (1608 Metric) 2A 100mOhm")
      (fields (field (name "Comment") "ferrite bead"))
      (libsource (lib "Schlib2") (part "BBHV00160808601Y00"))
    )
    (comp (ref "R1")
      (value "10k")
      (footprint "RC04025-L")
      (description "10 kOhms ±1% 0.1W, 1/10W Chip Resistor 0402 (1005 Metric) Automotive AEC-Q200 Thick Film")
      (fields (field (name "Comment") "ERJ-2RKF1002X"))
      (libsource (lib "") (part "R0402_10k_ERJ-2RKF1002X_1"))
    )
    (comp (ref "R2")
      (value "510")
      (footprint "RC04025-L")
      (description "510 Ohms ±1% 0.1W, 1/10W Chip Resistor 0402 (1005 Metric) Automotive AEC-Q200 Thick Film")
      (fields (field (name "Comment") "ERJ-2RKF5100X"))
      (libsource (lib "Schlib2") (part "R0402_510_ERJ-2RKF5100X"))
    )
    (comp (ref "R3")
      (value "4.7k")
      (footprint "RC04025-L")
      (description "4.7 kOhms ±1% 0.1W, 1/10W Chip Resistor 0402 (1005 Metric) Automotive AEC-Q200 Thick Film")
      (fields (field (name "Comment") "ERJ-2RKF4701X"))
      (libsource (lib "Schlib2") (part "R0402_4.7k_ERJ-2RKF4701X"))
    )
    (comp (ref "R4")
      (value "4.7k")
      (footprint "RC04025-L")
      (description "4.7 kOhms ±1% 0.1W, 1/10W Chip Resistor 0402 (1005 Metric) Automotive AEC-Q200 Thick Film")
      (fields (field (name "Comment") "ERJ-2RKF4701X"))
      (libsource (lib "Schlib2") (part "R0402_4.7k_ERJ-2RKF4701X"))
    )
    (comp (ref "R5")
      (value "100k")
      (footprint "RC04025-L")
      (description "100 kOhms ±1% 0.1W, 1/10W Chip Resistor 0402 (1005 Metric) Automotive AEC-Q200 Thick Film")
      (fields (field (name "Comment") "ERJ-2RKF1003X"))
      (libsource (lib "Schlib2") (part "R0402_100k_ERJ-2RKF1003X"))
    )
    (comp (ref "R6")
      (value "10k")
      (footprint "RC04025-L")
      (description "10 kOhms ±1% 0.1W, 1/10W Chip Resistor 0402 (1005 Metric) Automotive AEC-Q200 Thick Film")
      (fields (field (name "Comment") "ERJ-2RKF1002X"))
      (libsource (lib "") (part "R0402_10k_ERJ-2RKF1002X_2"))
    )
    (comp (ref "R7")
      (value "1k")
      (footprint "RC04025-L")
      (description "1 kOhms ±1% 0.1W, 1/10W Chip Resistor 0402 (1005 Metric) Automotive AEC-Q200 Thick Film")
      (fields (field (name "Comment") "ERJ-2RKF1001X"))
      (libsource (lib "Schlib2") (part "R0402_1k_ERJ-2RKF1001X"))
    )
    (comp (ref "R8")
      (value "390k")
      (footprint "RC04025-L")
      (description "390 kOhms ±1% 0.1W, 1/10W Chip Resistor 0402 (1005 Metric) Automotive AEC-Q200 Thick Film")
      (fields (field (name "Comment") "RK73H1ETTP3903F"))
      (libsource (lib "Schlib2") (part "R0402_390k_RK73H1ETTP3903F"))
    )
    (comp (ref "R9")
      (value "510")
      (footprint "RC04025-L")
      (description "510 Ohms ±1% 0.1W, 1/10W Chip Resistor 0402 (1005 Metric) Automotive AEC-Q200 Thick Film")
      (fields (field (name "Comment") "ERJ-2RKF5100X"))
      (libsource (lib "Schlib2") (part "R0402_510_ERJ-2RKF5100X"))
    )
    (comp (ref "R10")
      (value "169")
      (footprint "RC04025-L")
      (description "169 Ohms ±1% 0.1W, 1/10W Chip Resistor 0402 (1005 Metric) Automotive AEC-Q200 Thick Film")
      (fields (field (name "Comment") "ERJ-2RKF1690X"))
      (libsource (lib "Schlib2") (part "R0402_169_ERJ-2RKF1690X"))
    )
    (comp (ref "R11")
      (value "75")
      (footprint "RC04025-L")
      (description "75 Ohms ±5% 0.1W, 1/10W Chip Resistor 0402 (1005 Metric) Automotive AEC-Q200 Thick Film")
      (fields (field (name "Comment") "ERJ-2GEJ750X"))
      (libsource (lib "Schlib2") (part "R0402_75_ERJ-2GEJ750X"))
    )
    (comp (ref "R12")
      (value "10k")
      (footprint "RC04025-L")
      (description "10 kOhms ±1% 0.1W, 1/10W Chip Resistor 0402 (1005 Metric) Automotive AEC-Q200 Thick Film")
      (fields (field (name "Comment") "ERJ-2RKF1002X"))
      (libsource (lib "Schlib2") (part "R0402_10k_ERJ-2RKF1002X"))
    )
    (comp (ref "R14")
      (value "75")
      (footprint "RC04025-L")
      (description "75 Ohms ±5% 0.1W, 1/10W Chip Resistor 0402 (1005 Metric) Automotive AEC-Q200 Thick Film")
      (fields (field (name "Comment") "ERJ-2GEJ750X"))
      (libsource (lib "Schlib2") (part "R0402_75_ERJ-2GEJ750X"))
    )
    (comp (ref "R15")
      (value "75")
      (footprint "RC04025-L")
      (description "75 Ohms ±5% 0.1W, 1/10W Chip Resistor 0402 (1005 Metric) Automotive AEC-Q200 Thick Film")
      (fields (field (name "Comment") "ERJ-2GEJ750X"))
      (libsource (lib "Schlib2") (part "R0402_75_ERJ-2GEJ750X"))
    )
    (comp (ref "R16")
      (value "100")
      (footprint "RC04025-L")
      (description "100 Ohms ±1% 0.1W, 1/10W Chip Resistor 0402 (1005 Metric) Automotive AEC-Q200 Thick Film")
      (fields (field (name "Comment") "ERJ-2RKF1000X"))
      (libsource (lib "Schlib2") (part "R0402_100_ERJ-2RKF1000X"))
    )
    (comp (ref "R17")
      (value "100")
      (footprint "RC04025-L")
      (description "100 Ohms ±1% 0.1W, 1/10W Chip Resistor 0402 (1005 Metric) Automotive AEC-Q200 Thick Film")
      (fields (field (name "Comment") "ERJ-2RKF1000X"))
      (libsource (lib "Schlib2") (part "R0402_100_ERJ-2RKF1000X"))
    )
    (comp (ref "R18")
      (value "47k")
      (footprint "RC04025-L")
      (description "47 kOhms ±1% 0.1W, 1/10W Chip Resistor 0402 (1005 Metric) Automotive AEC-Q200 Thick Film")
      (fields (field (name "Comment") "ERJ-2RKF4702X"))
      (libsource (lib "Schlib2") (part "R0402_47k_ERJ-2RKF4702X"))
    )
    (comp (ref "R19")
      (value "47k")
      (footprint "RC04025-L")
      (description "47 kOhms ±1% 0.1W, 1/10W Chip Resistor 0402 (1005 Metric) Automotive AEC-Q200 Thick Film")
      (fields (field (name "Comment") "ERJ-2RKF4702X"))
      (libsource (lib "Schlib2") (part "R0402_47k_ERJ-2RKF4702X"))
    )
    (comp (ref "SB1")
      (value "Jumper SB")
      (footprint "SB0603")
      (description "Circuit Breaker Opened , for solder closing")
      (libsource (lib "Schlib2") (part "Jumper Opened"))
    )
    (comp (ref "SB2")
      (value "Jumper SB")
      (footprint "SB0603")
      (description "Circuit Breaker Opened , for solder closing")
      (libsource (lib "") (part "Jumper Opened_1"))
    )
    (comp (ref "VT1")
      (value "FDY3000NZ")
      (footprint "FAIR-SOT-563F-6-A_V")
      (description "Mosfet Array 20V 600mA 446mW Surface Mount SOT-563F")
      (libsource (lib "Schlib2") (part "FDY3000NZ"))
    )
    (comp (ref "XS1")
      (value "SM04B-GHS-TB")
      (footprint "SM04B-GHS-TB")
      (description "1.25mm pitch/Disconnectable Crimp style connectors")
      (fields (field (name "НАЗВА ЗА КД") "Роз'єм SM04B-GHS-TB(LF)(SN)"))
      (libsource (lib "Schlib2") (part "JST GH SM04B-GHS-TB"))
    )
    (comp (ref "XS2")
      (value "685119136923")
      (footprint "685119136923")
      (description "HDMI - Mini Receptacle Connector 19 Position Surface Mount, Right Angle; Through Hole")
      (libsource (lib "Schlib2") (part "685119136923"))
    )
    (comp (ref "XS3")
      (value "SM08B-GHS-TB")
      (footprint "SM08B-GHS-TB")
      (description "1.25x08 JST GH RA")
      (libsource (lib "Schlib2") (part "JST GH SM08B-GHS-TB"))
    )
    (comp (ref "XS4")
      (value "SM04B-GHS-TB")
      (footprint "SM04B-GHS-TB")
      (description "1.25mm pitch/Disconnectable Crimp style connectors")
      (fields (field (name "НАЗВА ЗА КД") "Роз'єм SM04B-GHS-TB(LF)(SN)"))
      (libsource (lib "Schlib2") (part "JST GH SM04B-GHS-TB"))
    )
    (comp (ref "XS5")
      (value "SM04B-GHS-TB")
      (footprint "SM04B-GHS-TB")
      (description "1.25mm pitch/Disconnectable Crimp style connectors")
      (fields (field (name "НАЗВА ЗА КД") "Роз'єм SM04B-GHS-TB(LF)(SN)"))
      (libsource (lib "Schlib2") (part "JST GH SM04B-GHS-TB"))
    )
    (comp (ref "ZQ1")
      (value "ABM11-28.63636MHZ-D2X-T3")
      (footprint "FP-ABM11-MFG")
      (description "28.63636 MHz ±20ppm Crystal 10pF 100 Ohms 4-SMD, No Lead")
      (libsource (lib "Schlib2") (part "ABM11-28.63636MHZ-D2X-T3"))
    )
  )
  (nets
    (net (code "1") (name "+3.3V_LVR_1") (class "Default")
      (node (ref "C22") (pin "2") (pinfunction "2_2") (pintype "passive"))
      (node (ref "C45") (pin "2") (pinfunction "2_2") (pintype "passive"))
      (node (ref "DA4") (pin "1") (pinfunction "OUT_1") (pintype "passive"))
      (node (ref "L1") (pin "1") (pinfunction "1_1") (pintype "passive"))
      (node (ref "L12") (pin "2") (pinfunction "2_2") (pintype "passive"))
      (node (ref "L13") (pin "2") (pinfunction "2_2") (pintype "passive"))
      (node (ref "L2") (pin "1") (pinfunction "1_1") (pintype "passive"))
      (node (ref "L3") (pin "1") (pinfunction "1_1") (pintype "passive"))
      (node (ref "L8") (pin "1") (pinfunction "1_1") (pintype "passive"))
    )
    (net (code "2") (name "/+1.8V_ LVR_1") (class "Default")
      (node (ref "C21") (pin "2") (pinfunction "2_2") (pintype "passive"))
      (node (ref "DA3") (pin "1") (pinfunction "OUT_1") (pintype "passive"))
      (node (ref "L6") (pin "2") (pinfunction "2_2") (pintype "passive"))
    )
    (net (code "3") (name "/+1.8V_ LVR_2") (class "Default")
      (node (ref "C42") (pin "2") (pinfunction "2_2") (pintype "passive"))
      (node (ref "C48") (pin "2") (pinfunction "2_2") (pintype "passive"))
      (node (ref "DA6") (pin "1") (pinfunction "OUT_1") (pintype "passive"))
      (node (ref "L11") (pin "1") (pinfunction "1_1") (pintype "passive"))
    )
    (net (code "4") (name "/+1.8V_ LVR_3") (class "Default")
      (node (ref "C76") (pin "2") (pinfunction "2_2") (pintype "passive"))
      (node (ref "DA1") (pin "1") (pinfunction "OUT_1") (pintype "passive"))
      (node (ref "L7") (pin "2") (pinfunction "2_2") (pintype "passive"))
    )
    (net (code "5") (name "/+1.8V_ PVDD_2") (class "Default")
      (node (ref "C41") (pin "2") (pinfunction "2_2") (pintype "passive"))
      (node (ref "C46") (pin "2") (pinfunction "2_2") (pintype "passive"))
      (node (ref "DA5") (pin "1") (pinfunction "OUT_1") (pintype "passive"))
      (node (ref "L9") (pin "1") (pinfunction "1_1") (pintype "passive"))
    )
    (net (code "6") (name "/+1.8V_PVDD_1") (class "Default")
      (node (ref "C20") (pin "2") (pinfunction "2_2") (pintype "passive"))
      (node (ref "DA2") (pin "1") (pinfunction "OUT_1") (pintype "passive"))
      (node (ref "L5") (pin "2") (pinfunction "2_2") (pintype "passive"))
    )
    (net (code "7") (name "/+3.3V_LVR_A") (class "Default")
      (node (ref "C43") (pin "2") (pinfunction "2_2") (pintype "passive"))
      (node (ref "C47") (pin "2") (pinfunction "2_2") (pintype "passive"))
      (node (ref "DA7") (pin "1") (pinfunction "OUT_1") (pintype "passive"))
      (node (ref "L10") (pin "1") (pinfunction "1_1") (pintype "passive"))
    )
    (net (code "8") (name "/+5V Power") (class "Default")
      (node (ref "DD2") (pin "64") (pinfunction "RXA_5V_64") (pintype "passive"))
      (node (ref "R5") (pin "2") (pinfunction "2_2") (pintype "passive"))
      (node (ref "R7") (pin "1") (pinfunction "1_1") (pintype "passive"))
      (node (ref "XS2") (pin "18") (pinfunction "+5V_Power_18") (pintype "passive"))
    )
    (net (code "9") (name "/+5V_in") (class "Default")
      (node (ref "C17") (pin "2") (pinfunction "2_2") (pintype "passive"))
      (node (ref "C18") (pin "2") (pinfunction "2_2") (pintype "passive"))
      (node (ref "C19") (pin "2") (pinfunction "2_2") (pintype "passive"))
      (node (ref "C37") (pin "2") (pinfunction "2_2") (pintype "passive"))
      (node (ref "C38") (pin "2") (pinfunction "2_2") (pintype "passive"))
      (node (ref "C39") (pin "2") (pinfunction "2_2") (pintype "passive"))
      (node (ref "C75") (pin "2") (pinfunction "2_2") (pintype "passive"))
      (node (ref "DA1") (pin "3") (pinfunction "EN_3") (pintype "passive"))
      (node (ref "DA1") (pin "4") (pinfunction "IN_4") (pintype "passive"))
      (node (ref "DA2") (pin "3") (pinfunction "EN_3") (pintype "passive"))
      (node (ref "DA2") (pin "4") (pinfunction "IN_4") (pintype "passive"))
      (node (ref "DA3") (pin "3") (pinfunction "EN_3") (pintype "passive"))
      (node (ref "DA3") (pin "4") (pinfunction "IN_4") (pintype "passive"))
      (node (ref "DA4") (pin "3") (pinfunction "EN_3") (pintype "passive"))
      (node (ref "DA4") (pin "4") (pinfunction "IN_4") (pintype "passive"))
      (node (ref "DA5") (pin "3") (pinfunction "EN_3") (pintype "passive"))
      (node (ref "DA5") (pin "4") (pinfunction "IN_4") (pintype "passive"))
      (node (ref "DA6") (pin "3") (pinfunction "EN_3") (pintype "passive"))
      (node (ref "DA6") (pin "4") (pinfunction "IN_4") (pintype "passive"))
      (node (ref "DA7") (pin "3") (pinfunction "EN_3") (pintype "passive"))
      (node (ref "DA7") (pin "4") (pinfunction "IN_4") (pintype "passive"))
      (node (ref "L4") (pin "2") (pinfunction "2_2") (pintype "passive"))
      (node (ref "XS4") (pin "3") (pinfunction "3_3") (pintype "passive"))
      (node (ref "XS4") (pin "4") (pinfunction "4_4") (pintype "passive"))
    )
    (net (code "10") (name "/CEC") (class "Default")
      (node (ref "DD2") (pin "61") (pinfunction "CEC_61") (pintype "passive"))
      (node (ref "XS2") (pin "14") (pinfunction "CEC_14") (pintype "passive"))
    )
    (net (code "11") (name "/CVDD1") (class "Default")
      (node (ref "C23") (pin "2") (pinfunction "2_2") (pintype "passive"))
      (node (ref "C24") (pin "2") (pinfunction "2_2") (pintype "passive"))
      (node (ref "C30") (pin "2") (pinfunction "2_2") (pintype "passive"))
      (node (ref "C31") (pin "2") (pinfunction "2_2") (pintype "passive"))
      (node (ref "DD2") (pin "14") (pinfunction "CVDD_14") (pintype "passive"))
      (node (ref "DD2") (pin "2") (pinfunction "CVDD_2") (pintype "passive"))
      (node (ref "L6") (pin "1") (pinfunction "1_1") (pintype "passive"))
    )
    (net (code "12") (name "/DVDD1") (class "Default")
      (node (ref "C25") (pin "2") (pinfunction "2_2") (pintype "passive"))
      (node (ref "C26") (pin "2") (pinfunction "2_2") (pintype "passive"))
      (node (ref "C27") (pin "2") (pinfunction "2_2") (pintype "passive"))
      (node (ref "C28") (pin "2") (pinfunction "2_2") (pintype "passive"))
      (node (ref "C32") (pin "2") (pinfunction "2_2") (pintype "passive"))
      (node (ref "C33") (pin "2") (pinfunction "2_2") (pintype "passive"))
      (node (ref "C34") (pin "2") (pinfunction "2_2") (pintype "passive"))
      (node (ref "C35") (pin "2") (pinfunction "2_2") (pintype "passive"))
      (node (ref "DD2") (pin "24") (pinfunction "DVDD_24") (pintype "passive"))
      (node (ref "DD2") (pin "40") (pinfunction "DVDD_40") (pintype "passive"))
      (node (ref "DD2") (pin "52") (pinfunction "DVDD_52") (pintype "passive"))
      (node (ref "DD2") (pin "60") (pinfunction "DVDD_60") (pintype "passive"))
      (node (ref "L7") (pin "1") (pinfunction "1_1") (pintype "passive"))
    )
    (net (code "13") (name "/DVDDIO1") (class "Default")
      (node (ref "C14") (pin "2") (pinfunction "2_2") (pintype "passive"))
      (node (ref "C15") (pin "2") (pinfunction "2_2") (pintype "passive"))
      (node (ref "C16") (pin "2") (pinfunction "2_2") (pintype "passive"))
      (node (ref "C7") (pin "2") (pinfunction "2_2") (pintype "passive"))
      (node (ref "C8") (pin "2") (pinfunction "2_2") (pintype "passive"))
      (node (ref "C9") (pin "2") (pinfunction "2_2") (pintype "passive"))
      (node (ref "DD2") (pin "23") (pinfunction "DVDDIO_23") (pintype "passive"))
      (node (ref "DD2") (pin "34") (pinfunction "DVDDIO_34") (pintype "passive"))
      (node (ref "DD2") (pin "44") (pinfunction "DVDDIO_44") (pintype "passive"))
      (node (ref "L3") (pin "2") (pinfunction "2_2") (pintype "passive"))
    )
    (net (code "14") (name "/HS") (class "Default")
      (node (ref "DD2") (pin "46") (pinfunction "HS_46") (pintype "passive"))
      (node (ref "DD3") (pin "33") (pinfunction "~{HSYNC}_33") (pintype "passive"))
    )
    (net (code "15") (name "/Hot Plug Detect {slash} HEAC-") (class "Default")
      (node (ref "DD2") (pin "1") (pinfunction "HPA_A/INT2_1") (pintype "passive"))
      (node (ref "R7") (pin "2") (pinfunction "2_2") (pintype "passive"))
      (node (ref "VT1") (pin "6") (pinfunction "D1_6") (pintype "passive"))
      (node (ref "XS2") (pin "19") (pinfunction "Hot_Plug_Detect_/_HEAC-_19") (pintype "passive"))
    )
    (net (code "16") (name "/I2S") (class "Default")
      (node (ref "DD2") (pin "48") (pinfunction "AP_48") (pintype "passive"))
      (node (ref "DD4") (pin "7") (pinfunction "PBDAT_7") (pintype "passive"))
    )
    (net (code "17") (name "/LED1") (class "Default")
      (node (ref "DD1") (pin "25") (pinfunction "PC4_25") (pintype "passive"))
      (node (ref "HL1") (pin "2") (pinfunction "A_2") (pintype "passive"))
    )
    (net (code "18") (name "/LLC") (class "Default")
      (node (ref "DD2") (pin "25") (pinfunction "LLC_25") (pintype "passive"))
      (node (ref "DD3") (pin "19") (pinfunction "CLKIN_19") (pintype "passive"))
    )
    (net (code "19") (name "/LRCLK") (class "Default")
      (node (ref "DD2") (pin "50") (pinfunction "LRCLK_50") (pintype "passive"))
      (node (ref "DD4") (pin "8") (pinfunction "PBLRC_8") (pintype "passive"))
    )
    (net (code "20") (name "/MCLK") (class "Default")
      (node (ref "DD2") (pin "51") (pinfunction "MCLK/INT2_51") (pintype "passive"))
      (node (ref "DD4") (pin "1") (pinfunction "MCLK/XTI_1") (pintype "passive"))
    )
    (net (code "21") (name "/MCU_VDD") (class "Default")
      (node (ref "C10") (pin "2") (pinfunction "2_2") (pintype "passive"))
      (node (ref "C3") (pin "2") (pinfunction "2_2") (pintype "passive"))
      (node (ref "DD1") (pin "7") (pinfunction "VDD/VREF+_7") (pintype "passive"))
      (node (ref "L1") (pin "2") (pinfunction "2_2") (pintype "passive"))
      (node (ref "R1") (pin "1") (pinfunction "1_1") (pintype "passive"))
      (node (ref "R3") (pin "2") (pinfunction "2_2") (pintype "passive"))
      (node (ref "R4") (pin "2") (pinfunction "2_2") (pintype "passive"))
      (node (ref "XS1") (pin "4") (pinfunction "4_4") (pintype "passive"))
      (node (ref "XS5") (pin "4") (pinfunction "4_4") (pintype "passive"))
    )
    (net (code "22") (name "/P0") (class "Default")
      (node (ref "DD2") (pin "43") (pinfunction "P0_43") (pintype "passive"))
      (node (ref "DD3") (pin "34") (pinfunction "P0_34") (pintype "passive"))
    )
    (net (code "23") (name "/P1") (class "Default")
      (node (ref "DD2") (pin "42") (pinfunction "P1_42") (pintype "passive"))
      (node (ref "DD3") (pin "37") (pinfunction "P1_37") (pintype "passive"))
    )
    (net (code "24") (name "/P2") (class "Default")
      (node (ref "DD2") (pin "41") (pinfunction "P2_41") (pintype "passive"))
      (node (ref "DD3") (pin "38") (pinfunction "P2_38") (pintype "passive"))
    )
    (net (code "25") (name "/P3") (class "Default")
      (node (ref "DD2") (pin "39") (pinfunction "P3_39") (pintype "passive"))
      (node (ref "DD3") (pin "39") (pinfunction "P3_39") (pintype "passive"))
    )
    (net (code "26") (name "/P4") (class "Default")
      (node (ref "DD2") (pin "38") (pinfunction "P4_38") (pintype "passive"))
      (node (ref "DD3") (pin "2") (pinfunction "P4_2") (pintype "passive"))
    )
    (net (code "27") (name "/P5") (class "Default")
      (node (ref "DD2") (pin "37") (pinfunction "P5_37") (pintype "passive"))
      (node (ref "DD3") (pin "3") (pinfunction "P5_3") (pintype "passive"))
    )
    (net (code "28") (name "/P6") (class "Default")
      (node (ref "DD2") (pin "36") (pinfunction "P6_36") (pintype "passive"))
      (node (ref "DD3") (pin "4") (pinfunction "P6_4") (pintype "passive"))
    )
    (net (code "29") (name "/P7") (class "Default")
      (node (ref "DD2") (pin "35") (pinfunction "P7_35") (pintype "passive"))
      (node (ref "DD3") (pin "5") (pinfunction "P7_5") (pintype "passive"))
    )
    (net (code "30") (name "/P8") (class "Default")
      (node (ref "DD2") (pin "33") (pinfunction "P8_33") (pintype "passive"))
      (node (ref "DD3") (pin "8") (pinfunction "P8_8") (pintype "passive"))
    )
    (net (code "31") (name "/P9") (class "Default")
      (node (ref "DD2") (pin "32") (pinfunction "P9_32") (pintype "passive"))
      (node (ref "DD3") (pin "9") (pinfunction "P9_9") (pintype "passive"))
    )
    (net (code "32") (name "/P10") (class "Default")
      (node (ref "DD2") (pin "31") (pinfunction "P10_31") (pintype "passive"))
      (node (ref "DD3") (pin "10") (pinfunction "P10_10") (pintype "passive"))
    )
    (net (code "33") (name "/P11") (class "Default")
      (node (ref "DD2") (pin "30") (pinfunction "P11_30") (pintype "passive"))
      (node (ref "DD3") (pin "11") (pinfunction "P11_11") (pintype "passive"))
    )
    (net (code "34") (name "/P12") (class "Default")
      (node (ref "DD2") (pin "29") (pinfunction "P12_29") (pintype "passive"))
      (node (ref "DD3") (pin "15") (pinfunction "P12_15") (pintype "passive"))
    )
    (net (code "35") (name "/P13") (class "Default")
      (node (ref "DD2") (pin "28") (pinfunction "P13_28") (pintype "passive"))
      (node (ref "DD3") (pin "16") (pinfunction "P13_16") (pintype "passive"))
    )
    (net (code "36") (name "/P14") (class "Default")
      (node (ref "DD2") (pin "27") (pinfunction "P14_27") (pintype "passive"))
      (node (ref "DD3") (pin "17") (pinfunction "P14_17") (pintype "passive"))
    )
    (net (code "37") (name "/P15") (class "Default")
      (node (ref "DD2") (pin "26") (pinfunction "P15_26") (pintype "passive"))
      (node (ref "DD3") (pin "18") (pinfunction "P15_18") (pintype "passive"))
    )
    (net (code "38") (name "/PVDD1") (class "Default")
      (node (ref "C29") (pin "2") (pinfunction "2_2") (pintype "passive"))
      (node (ref "C36") (pin "2") (pinfunction "2_2") (pintype "passive"))
      (node (ref "DD2") (pin "57") (pinfunction "PVDD_57") (pintype "passive"))
      (node (ref "L5") (pin "1") (pinfunction "1_1") (pintype "passive"))
    )
    (net (code "39") (name "/SCL") (class "Default")
      (node (ref "DD2") (pin "62") (pinfunction "DDCA_SCL_62") (pintype "passive"))
      (node (ref "R6") (pin "2") (pinfunction "2_2") (pintype "passive"))
    )
    (net (code "40") (name "/SCLK") (class "Default")
      (node (ref "DD2") (pin "49") (pinfunction "SCLK/INT2_49") (pintype "passive"))
      (node (ref "DD4") (pin "6") (pinfunction "BCLK_6") (pintype "passive"))
    )
    (net (code "41") (name "/SR_reset") (class "Default")
      (node (ref "DD1") (pin "1") (pinfunction "NRST/PA1_1") (pintype "passive"))
      (node (ref "XS1") (pin "3") (pinfunction "3_3") (pintype "passive"))
    )
    (net (code "42") (name "/SWIM") (class "Default")
      (node (ref "DD1") (pin "28") (pinfunction "PA0_28") (pintype "passive"))
      (node (ref "XS1") (pin "2") (pinfunction "2_2") (pintype "passive"))
    )
    (net (code "43") (name "/Select") (class "Default")
      (node (ref "DD1") (pin "23") (pinfunction "PC2_23") (pintype "passive"))
      (node (ref "R1") (pin "2") (pinfunction "2_2") (pintype "passive"))
      (node (ref "SB1") (pin "2") (pinfunction "2_2") (pintype "passive"))
    )
    (net (code "44") (name "/TMDS Clock_N") (class "Default")
      (node (ref "DD2") (pin "3") (pinfunction "RXA_C-_3") (pintype "passive"))
      (node (ref "XS2") (pin "12") (pinfunction "TMDS_Clock-_12") (pintype "passive"))
    )
    (net (code "45") (name "/TMDS Clock_P") (class "Default")
      (node (ref "DD2") (pin "4") (pinfunction "RXA_C+_4") (pintype "passive"))
      (node (ref "XS2") (pin "11") (pinfunction "TMDS_Clock+_11") (pintype "passive"))
    )
    (net (code "46") (name "/TMDS Data0_N") (class "Default")
      (node (ref "DD2") (pin "6") (pinfunction "RXA_0-_6") (pintype "passive"))
      (node (ref "XS2") (pin "9") (pinfunction "TMDS_Data0-_9") (pintype "passive"))
    )
    (net (code "47") (name "/TMDS Data0_P") (class "Default")
      (node (ref "DD2") (pin "7") (pinfunction "RXA_0+_7") (pintype "passive"))
      (node (ref "XS2") (pin "8") (pinfunction "TMDS_Data0+_8") (pintype "passive"))
    )
    (net (code "48") (name "/TMDS Data1_N") (class "Default")
      (node (ref "DD2") (pin "9") (pinfunction "RXA_1-_9") (pintype "passive"))
      (node (ref "XS2") (pin "6") (pinfunction "TMDS_Data1-_6") (pintype "passive"))
    )
    (net (code "49") (name "/TMDS Data1_P") (class "Default")
      (node (ref "DD2") (pin "10") (pinfunction "RXA_1+_10") (pintype "passive"))
      (node (ref "XS2") (pin "5") (pinfunction "TMDS_Data1+_5") (pintype "passive"))
    )
    (net (code "50") (name "/TMDS Data2_N") (class "Default")
      (node (ref "DD2") (pin "12") (pinfunction "RXA_2-_12") (pintype "passive"))
      (node (ref "XS2") (pin "3") (pinfunction "TMDS_Data2-_3") (pintype "passive"))
    )
    (net (code "51") (name "/TMDS Data2_P") (class "Default")
      (node (ref "DD2") (pin "13") (pinfunction "RXA_2+_13") (pintype "passive"))
      (node (ref "XS2") (pin "2") (pinfunction "TMDS_Data2+_2") (pintype "passive"))
    )
    (net (code "52") (name "/UART1_RX") (class "Default")
      (node (ref "DD1") (pin "3") (pinfunction "PA3_3") (pintype "passive"))
      (node (ref "XS5") (pin "3") (pinfunction "3_3") (pintype "passive"))
    )
    (net (code "53") (name "/UART1_TX") (class "Default")
      (node (ref "DD1") (pin "2") (pinfunction "PA2_2") (pintype "passive"))
      (node (ref "XS5") (pin "2") (pinfunction "2_2") (pintype "passive"))
    )
    (net (code "54") (name "/VDD1") (class "Default")
      (node (ref "C52") (pin "2") (pinfunction "2_2") (pintype "passive"))
      (node (ref "C56") (pin "2") (pinfunction "2_2") (pintype "passive"))
      (node (ref "C57") (pin "2") (pinfunction "2_2") (pintype "passive"))
      (node (ref "C61") (pin "2") (pinfunction "2_2") (pintype "passive"))
      (node (ref "C62") (pin "2") (pinfunction "2_2") (pintype "passive"))
      (node (ref "DD3") (pin "35") (pinfunction "VDD_35") (pintype "power_in"))
      (node (ref "DD3") (pin "6") (pinfunction "VDD_6") (pintype "power_in"))
      (node (ref "L11") (pin "2") (pinfunction "2_2") (pintype "passive"))
    )
    (net (code "55") (name "/VS") (class "Default")
      (node (ref "DD2") (pin "47") (pinfunction "VS/FIELD/ALSB_47") (pintype "passive"))
      (node (ref "DD3") (pin "32") (pinfunction "~{VSYNC}_32") (pintype "passive"))
    )
    (net (code "56") (name "5V_out") (class "Default")
      (node (ref "C1") (pin "2") (pinfunction "2_2") (pintype "passive"))
      (node (ref "C2") (pin "2") (pinfunction "2_2") (pintype "passive"))
      (node (ref "L4") (pin "1") (pinfunction "1_1") (pintype "passive"))
      (node (ref "XS3") (pin "2") (pinfunction "2_2") (pintype "passive"))
    )
    (net (code "57") (name "AGND") (class "Default")
      (node (ref "C1") (pin "1") (pinfunction "1_1") (pintype "passive"))
      (node (ref "C2") (pin "1") (pinfunction "1_1") (pintype "passive"))
      (node (ref "C51") (pin "1") (pinfunction "1_1") (pintype "passive"))
      (node (ref "C55") (pin "1") (pinfunction "1_1") (pintype "passive"))
      (node (ref "C60") (pin "1") (pinfunction "1_1") (pintype "passive"))
      (node (ref "C63") (pin "1") (pinfunction "1_1") (pintype "passive"))
      (node (ref "C70") (pin "2") (pinfunction "2_2") (pintype "passive"))
      (node (ref "C71") (pin "1") (pinfunction "1_1") (pintype "passive"))
      (node (ref "C73") (pin "2") (pinfunction "2_2") (pintype "passive"))
      (node (ref "C74") (pin "1") (pinfunction "1_1") (pintype "passive"))
      (node (ref "DD3") (pin "24") (pinfunction "AGND_24") (pintype "power_in"))
      (node (ref "DD3") (pin "41") (pinfunction "EP_41") (pintype "power_in"))
      (node (ref "DD4") (pin "14") (pinfunction "AGND_14") (pintype "passive"))
      (node (ref "L14") (pin "1") (pinfunction "1_1") (pintype "passive"))
      (node (ref "R11") (pin "1") (pinfunction "1_1") (pintype "passive"))
      (node (ref "R14") (pin "1") (pinfunction "1_1") (pintype "passive"))
      (node (ref "R15") (pin "1") (pinfunction "1_1") (pintype "passive"))
      (node (ref "R18") (pin "1") (pinfunction "1_1") (pintype "passive"))
      (node (ref "R19") (pin "1") (pinfunction "1_1") (pintype "passive"))
      (node (ref "R9") (pin "2") (pinfunction "2_2") (pintype "passive"))
      (node (ref "XS3") (pin "1") (pinfunction "1_1") (pintype "passive"))
      (node (ref "XS3") (pin "3") (pinfunction "3_3") (pintype "passive"))
      (node (ref "XS3") (pin "5") (pinfunction "5_5") (pintype "passive"))
      (node (ref "XS3") (pin "7") (pinfunction "7_7") (pintype "passive"))
      (node (ref "XS3") (pin "M") (pinfunction "M_M") (pintype "passive"))
    )
    (net (code "58") (name "CV_out") (class "Default")
      (node (ref "DD3") (pin "28") (pinfunction "DAC1_28") (pintype "passive"))
      (node (ref "R15") (pin "2") (pinfunction "2_2") (pintype "passive"))
      (node (ref "XS3") (pin "4") (pinfunction "4_4") (pintype "passive"))
    )
    (net (code "59") (name "GND") (class "Default")
      (node (ref "C10") (pin "1") (pinfunction "1_1") (pintype "passive"))
      (node (ref "C11") (pin "1") (pinfunction "1_1") (pintype "passive"))
      (node (ref "C12") (pin "1") (pinfunction "1_1") (pintype "passive"))
      (node (ref "C13") (pin "1") (pinfunction "1_1") (pintype "passive"))
      (node (ref "C14") (pin "1") (pinfunction "1_1") (pintype "passive"))
      (node (ref "C15") (pin "1") (pinfunction "1_1") (pintype "passive"))
      (node (ref "C16") (pin "1") (pinfunction "1_1") (pintype "passive"))
      (node (ref "C17") (pin "1") (pinfunction "1_1") (pintype "passive"))
      (node (ref "C18") (pin "1") (pinfunction "1_1") (pintype "passive"))
      (node (ref "C19") (pin "1") (pinfunction "1_1") (pintype "passive"))
      (node (ref "C20") (pin "1") (pinfunction "1_1") (pintype "passive"))
      (node (ref "C21") (pin "1") (pinfunction "1_1") (pintype "passive"))
      (node (ref "C22") (pin "1") (pinfunction "1_1") (pintype "passive"))
      (node (ref "C23") (pin "1") (pinfunction "1_1") (pintype "passive"))
      (node (ref "C24") (pin "1") (pinfunction "1_1") (pintype "passive"))
      (node (ref "C25") (pin "1") (pinfunction "1_1") (pintype "passive"))
      (node (ref "C26") (pin "1") (pinfunction "1_1") (pintype "passive"))
      (node (ref "C27") (pin "1") (pinfunction "1_1") (pintype "passive"))
      (node (ref "C28") (pin "1") (pinfunction "1_1") (pintype "passive"))
      (node (ref "C29") (pin "1") (pinfunction "1_1") (pintype "passive"))
      (node (ref "C3") (pin "1") (pinfunction "1_1") (pintype "passive"))
      (node (ref "C30") (pin "1") (pinfunction "1_1") (pintype "passive"))
      (node (ref "C31") (pin "1") (pinfunction "1_1") (pintype "passive"))
      (node (ref "C32") (pin "1") (pinfunction "1_1") (pintype "passive"))
      (node (ref "C33") (pin "1") (pinfunction "1_1") (pintype "passive"))
      (node (ref "C34") (pin "1") (pinfunction "1_1") (pintype "passive"))
      (node (ref "C35") (pin "1") (pinfunction "1_1") (pintype "passive"))
      (node (ref "C36") (pin "1") (pinfunction "1_1") (pintype "passive"))
      (node (ref "C37") (pin "1") (pinfunction "1_1") (pintype "passive"))
      (node (ref "C38") (pin "1") (pinfunction "1_1") (pintype "passive"))
      (node (ref "C39") (pin "1") (pinfunction "1_1") (pintype "passive"))
      (node (ref "C4") (pin "1") (pinfunction "1_1") (pintype "passive"))
      (node (ref "C40") (pin "1") (pinfunction "1_1") (pintype "passive"))
      (node (ref "C41") (pin "1") (pinfunction "1_1") (pintype "passive"))
      (node (ref "C42") (pin "1") (pinfunction "1_1") (pintype "passive"))
      (node (ref "C43") (pin "1") (pinfunction "1_1") (pintype "passive"))
      (node (ref "C44") (pin "1") (pinfunction "1_1") (pintype "passive"))
      (node (ref "C45") (pin "1") (pinfunction "1_1") (pintype "passive"))
      (node (ref "C46") (pin "1") (pinfunction "1_1") (pintype "passive"))
      (node (ref "C47") (pin "1") (pinfunction "1_1") (pintype "passive"))
      (node (ref "C48") (pin "1") (pinfunction "1_1") (pintype "passive"))
      (node (ref "C49") (pin "1") (pinfunction "1_1") (pintype "passive"))
      (node (ref "C5") (pin "1") (pinfunction "1_1") (pintype "passive"))
      (node (ref "C50") (pin "1") (pinfunction "1_1") (pintype "passive"))
      (node (ref "C52") (pin "1") (pinfunction "1_1") (pintype "passive"))
      (node (ref "C53") (pin "1") (pinfunction "1_1") (pintype "passive"))
      (node (ref "C54") (pin "1") (pinfunction "1_1") (pintype "passive"))
      (node (ref "C56") (pin "1") (pinfunction "1_1") (pintype "passive"))
      (node (ref "C57") (pin "1") (pinfunction "1_1") (pintype "passive"))
      (node (ref "C58") (pin "1") (pinfunction "1_1") (pintype "passive"))
      (node (ref "C59") (pin "1") (pinfunction "1_1") (pintype "passive"))
      (node (ref "C6") (pin "1") (pinfunction "1_1") (pintype "passive"))
      (node (ref "C61") (pin "1") (pinfunction "1_1") (pintype "passive"))
      (node (ref "C62") (pin "1") (pinfunction "1_1") (pintype "passive"))
      (node (ref "C67") (pin "1") (pinfunction "1_1") (pintype "passive"))
      (node (ref "C7") (pin "1") (pinfunction "1_1") (pintype "passive"))
      (node (ref "C72") (pin "1") (pinfunction "1_1") (pintype "passive"))
      (node (ref "C75") (pin "1") (pinfunction "1_1") (pintype "passive"))
      (node (ref "C76") (pin "1") (pinfunction "1_1") (pintype "passive"))
      (node (ref "C8") (pin "1") (pinfunction "1_1") (pintype "passive"))
      (node (ref "C9") (pin "1") (pinfunction "1_1") (pintype "passive"))
      (node (ref "DA1") (pin "2") (pinfunction "GND_2") (pintype "passive"))
      (node (ref "DA1") (pin "5") (pinfunction "EPAD_5") (pintype "passive"))
      (node (ref "DA2") (pin "2") (pinfunction "GND_2") (pintype "passive"))
      (node (ref "DA2") (pin "5") (pinfunction "EPAD_5") (pintype "passive"))
      (node (ref "DA3") (pin "2") (pinfunction "GND_2") (pintype "passive"))
      (node (ref "DA3") (pin "5") (pinfunction "EPAD_5") (pintype "passive"))
      (node (ref "DA4") (pin "2") (pinfunction "GND_2") (pintype "passive"))
      (node (ref "DA4") (pin "5") (pinfunction "EPAD_5") (pintype "passive"))
      (node (ref "DA5") (pin "2") (pinfunction "GND_2") (pintype "passive"))
      (node (ref "DA5") (pin "5") (pinfunction "EPAD_5") (pintype "passive"))
      (node (ref "DA6") (pin "2") (pinfunction "GND_2") (pintype "passive"))
      (node (ref "DA6") (pin "5") (pinfunction "EPAD_5") (pintype "passive"))
      (node (ref "DA7") (pin "2") (pinfunction "GND_2") (pintype "passive"))
      (node (ref "DA7") (pin "5") (pinfunction "EPAD_5") (pintype "passive"))
      (node (ref "DD1") (pin "6") (pinfunction "VSS/VREF-_6") (pintype "passive"))
      (node (ref "DD2") (pin "65") (pinfunction "GND_65") (pintype "passive"))
      (node (ref "DD3") (pin "21") (pinfunction "PGND_21") (pintype "power_in"))
      (node (ref "DD3") (pin "36") (pinfunction "DGND_36") (pintype "power_in"))
      (node (ref "DD3") (pin "40") (pinfunction "GND_IO_40") (pintype "power_in"))
      (node (ref "DD3") (pin "7") (pinfunction "DGND_7") (pintype "power_in"))
      (node (ref "DD4") (pin "21") (pinfunction "GND_Pad_21") (pintype "passive"))
      (node (ref "DD4") (pin "3") (pinfunction "DGND_3") (pintype "passive"))
      (node (ref "L14") (pin "2") (pinfunction "2_2") (pintype "passive"))
      (node (ref "R2") (pin "2") (pinfunction "2_2") (pintype "passive"))
      (node (ref "R6") (pin "1") (pinfunction "1_1") (pintype "passive"))
      (node (ref "SB1") (pin "1") (pinfunction "1_1") (pintype "passive"))
      (node (ref "SB2") (pin "1") (pinfunction "1_1") (pintype "passive"))
      (node (ref "VT1") (pin "1") (pinfunction "S1_1") (pintype "passive"))
      (node (ref "VT1") (pin "4") (pinfunction "S2_4") (pintype "passive"))
      (node (ref "XS1") (pin "1") (pinfunction "1_1") (pintype "passive"))
      (node (ref "XS1") (pin "M") (pinfunction "M_M") (pintype "passive"))
      (node (ref "XS2") (pin "1") (pinfunction "TMDS_Data2_Shield_1") (pintype "passive"))
      (node (ref "XS2") (pin "10") (pinfunction "TMDS_Clock_Shield_10") (pintype "passive"))
      (node (ref "XS2") (pin "13") (pinfunction "DDC_/_CEC_Ground_/_HEAC_Shield_13") (pintype "passive"))
      (node (ref "XS2") (pin "4") (pinfunction "TMDS_Data1_Shield_4") (pintype "passive"))
      (node (ref "XS2") (pin "7") (pinfunction "TMDS_Data0_Shield_7") (pintype "passive"))
      (node (ref "XS2") (pin "Shell") (pinfunction "Shield_Shell") (pintype "passive"))
      (node (ref "XS4") (pin "1") (pinfunction "1_1") (pintype "passive"))
      (node (ref "XS4") (pin "2") (pinfunction "2_2") (pintype "passive"))
      (node (ref "XS4") (pin "M") (pinfunction "M_M") (pintype "passive"))
      (node (ref "XS5") (pin "1") (pinfunction "1_1") (pintype "passive"))
      (node (ref "XS5") (pin "M") (pinfunction "M_M") (pintype "passive"))
      (node (ref "ZQ1") (pin "2") (pinfunction "GND_2") (pintype "passive"))
      (node (ref "ZQ1") (pin "4") (pinfunction "GND_4") (pintype "passive"))
    )
    (net (code "60") (name "Lout") (class "Default")
      (node (ref "R16") (pin "2") (pinfunction "2_2") (pintype "passive"))
      (node (ref "XS3") (pin "6") (pinfunction "6_6") (pintype "passive"))
    )
    (net (code "61") (name "Net-(C66-Pad1)") (class "Default")
      (node (ref "C66") (pin "1") (pinfunction "1_1") (pintype "passive"))
      (node (ref "R10") (pin "2") (pinfunction "2_2") (pintype "passive"))
    )
    (net (code "62") (name "Net-(C68-Pad1)") (class "Default")
      (node (ref "C68") (pin "1") (pinfunction "1_1") (pintype "passive"))
      (node (ref "R16") (pin "1") (pinfunction "1_1") (pintype "passive"))
      (node (ref "R18") (pin "2") (pinfunction "2_2") (pintype "passive"))
    )
    (net (code "63") (name "Net-(C69-Pad1)") (class "Default")
      (node (ref "C69") (pin "1") (pinfunction "1_1") (pintype "passive"))
      (node (ref "R17") (pin "1") (pinfunction "1_1") (pintype "passive"))
      (node (ref "R19") (pin "2") (pinfunction "2_2") (pintype "passive"))
    )
    (net (code "64") (name "Net-(DD2A-XTALN)") (class "Default")
      (node (ref "C44") (pin "2") (pinfunction "2_2") (pintype "passive"))
      (node (ref "DD2") (pin "59") (pinfunction "XTALN_59") (pintype "passive"))
      (node (ref "R8") (pin "2") (pinfunction "2_2") (pintype "passive"))
      (node (ref "ZQ1") (pin "3") (pinfunction "OSC2_3") (pintype "passive"))
    )
    (net (code "65") (name "Net-(DD2A-XTALP)") (class "Default")
      (node (ref "C40") (pin "2") (pinfunction "2_2") (pintype "passive"))
      (node (ref "DD2") (pin "58") (pinfunction "XTALP_58") (pintype "passive"))
      (node (ref "R8") (pin "1") (pinfunction "1_1") (pintype "passive"))
      (node (ref "ZQ1") (pin "1") (pinfunction "OSC1_1") (pintype "passive"))
    )
    (net (code "66") (name "Net-(DD3A-ALSB)") (class "Default")
      (node (ref "DD3") (pin "12") (pinfunction "ALSB_12") (pintype "passive"))
      (node (ref "R12") (pin "2") (pinfunction "2_2") (pintype "passive"))
      (node (ref "SB2") (pin "2") (pinfunction "2_2") (pintype "passive"))
    )
    (net (code "67") (name "Net-(DD3A-COMP)") (class "Default")
      (node (ref "C64") (pin "2") (pinfunction "2_2") (pintype "passive"))
      (node (ref "DD3") (pin "29") (pinfunction "COMP_29") (pintype "passive"))
    )
    (net (code "68") (name "Net-(DD3A-DAC2)") (class "Default")
      (node (ref "DD3") (pin "27") (pinfunction "DAC2_27") (pintype "passive"))
      (node (ref "R14") (pin "2") (pinfunction "2_2") (pintype "passive"))
    )
    (net (code "69") (name "Net-(DD3A-DAC3)") (class "Default")
      (node (ref "DD3") (pin "26") (pinfunction "DAC3_26") (pintype "passive"))
      (node (ref "R11") (pin "2") (pinfunction "2_2") (pintype "passive"))
    )
    (net (code "70") (name "Net-(DD3A-EXT_LF)") (class "Default")
      (node (ref "C65") (pin "1") (pinfunction "1_1") (pintype "passive"))
      (node (ref "DD3") (pin "22") (pinfunction "EXT_LF_22") (pintype "passive"))
      (node (ref "R10") (pin "1") (pinfunction "1_1") (pintype "passive"))
    )
    (net (code "71") (name "Net-(DD3A-RSET)") (class "Default")
      (node (ref "DD3") (pin "30") (pinfunction "RSET_30") (pintype "passive"))
      (node (ref "R9") (pin "1") (pinfunction "1_1") (pintype "passive"))
    )
    (net (code "72") (name "Net-(DD4-AVDD)") (class "Default")
      (node (ref "C71") (pin "2") (pinfunction "2_2") (pintype "passive"))
      (node (ref "C74") (pin "2") (pinfunction "2_2") (pintype "passive"))
      (node (ref "DD4") (pin "13") (pinfunction "AVDD_13") (pintype "passive"))
      (node (ref "L12") (pin "1") (pinfunction "1_1") (pintype "passive"))
    )
    (net (code "73") (name "Net-(DD4-DVDD)") (class "Default")
      (node (ref "C67") (pin "2") (pinfunction "2_2") (pintype "passive"))
      (node (ref "C72") (pin "2") (pinfunction "2_2") (pintype "passive"))
      (node (ref "DD4") (pin "4") (pinfunction "DVDD_4") (pintype "passive"))
      (node (ref "L13") (pin "1") (pinfunction "1_1") (pintype "passive"))
    )
    (net (code "74") (name "Net-(DD4-LOUT)") (class "Default")
      (node (ref "C68") (pin "2") (pinfunction "2_2") (pintype "passive"))
      (node (ref "DD4") (pin "11") (pinfunction "LOUT_11") (pintype "passive"))
    )
    (net (code "75") (name "Net-(DD4-ROUT)") (class "Default")
      (node (ref "C69") (pin "2") (pinfunction "2_2") (pintype "passive"))
      (node (ref "DD4") (pin "12") (pinfunction "ROUT_12") (pintype "passive"))
    )
    (net (code "76") (name "Net-(DD4-VMID)") (class "Default")
      (node (ref "C70") (pin "1") (pinfunction "1_1") (pintype "passive"))
      (node (ref "C73") (pin "1") (pinfunction "1_1") (pintype "passive"))
      (node (ref "DD4") (pin "15") (pinfunction "VMID_15") (pintype "passive"))
    )
    (net (code "77") (name "Net-(HL1-K)") (class "Default")
      (node (ref "HL1") (pin "1") (pinfunction "K_1") (pintype "passive"))
      (node (ref "R2") (pin "1") (pinfunction "1_1") (pintype "passive"))
    )
    (net (code "78") (name "Net-(VT1A-G1)") (class "Default")
      (node (ref "R5") (pin "1") (pinfunction "1_1") (pintype "passive"))
      (node (ref "VT1") (pin "2") (pinfunction "G1_2") (pintype "passive"))
      (node (ref "VT1") (pin "3") (pinfunction "D2_3") (pintype "passive"))
    )
    (net (code "79") (name "PVDD2") (class "Default")
      (node (ref "C50") (pin "2") (pinfunction "2_2") (pintype "passive"))
      (node (ref "C54") (pin "2") (pinfunction "2_2") (pintype "passive"))
      (node (ref "C59") (pin "2") (pinfunction "2_2") (pintype "passive"))
      (node (ref "C65") (pin "2") (pinfunction "2_2") (pintype "passive"))
      (node (ref "C66") (pin "2") (pinfunction "2_2") (pintype "passive"))
      (node (ref "DD3") (pin "23") (pinfunction "PVDD_23") (pintype "power_in"))
      (node (ref "L9") (pin "2") (pinfunction "2_2") (pintype "passive"))
    )
    (net (code "80") (name "RESET_ADV7393") (class "Default")
      (node (ref "DD1") (pin "13") (pinfunction "PB1_13") (pintype "passive"))
      (node (ref "DD3") (pin "20") (pinfunction "~{RESET}_20") (pintype "passive"))
    )
    (net (code "81") (name "RESET_ADV7611") (class "Default")
      (node (ref "DD1") (pin "12") (pinfunction "PB0_12") (pintype "passive"))
      (node (ref "DD2") (pin "56") (pinfunction "~{RESET}_56") (pintype "passive"))
    )
    (net (code "82") (name "Rout") (class "Default")
      (node (ref "R17") (pin "2") (pinfunction "2_2") (pintype "passive"))
      (node (ref "XS3") (pin "8") (pinfunction "8_8") (pintype "passive"))
    )
    (net (code "83") (name "SCL_ADV7393") (class "Default")
      (node (ref "DD1") (pin "22") (pinfunction "PC1_22") (pintype "passive"))
      (node (ref "DD2") (pin "53") (pinfunction "SCL_53") (pintype "passive"))
      (node (ref "DD3") (pin "14") (pinfunction "SCL_14") (pintype "passive"))
      (node (ref "DD4") (pin "18") (pinfunction "SDIN_18") (pintype "passive"))
      (node (ref "R4") (pin "1") (pinfunction "1_1") (pintype "passive"))
    )
    (net (code "84") (name "SDA_ADV7393") (class "Default")
      (node (ref "DD1") (pin "21") (pinfunction "PC0_21") (pintype "passive"))
      (node (ref "DD2") (pin "54") (pinfunction "SDA_54") (pintype "passive"))
      (node (ref "DD3") (pin "13") (pinfunction "SDA_13") (pintype "passive"))
      (node (ref "DD4") (pin "19") (pinfunction "SCLK_19") (pintype "passive"))
      (node (ref "R3") (pin "1") (pinfunction "1_1") (pintype "passive"))
    )
    (net (code "85") (name "TVDD1") (class "Default")
      (node (ref "C11") (pin "2") (pinfunction "2_2") (pintype "passive"))
      (node (ref "C12") (pin "2") (pinfunction "2_2") (pintype "passive"))
      (node (ref "C13") (pin "2") (pinfunction "2_2") (pintype "passive"))
      (node (ref "C4") (pin "2") (pinfunction "2_2") (pintype "passive"))
      (node (ref "C5") (pin "2") (pinfunction "2_2") (pintype "passive"))
      (node (ref "C6") (pin "2") (pinfunction "2_2") (pintype "passive"))
      (node (ref "DD2") (pin "11") (pinfunction "TVDD_11") (pintype "passive"))
      (node (ref "DD2") (pin "5") (pinfunction "TVDD_5") (pintype "passive"))
      (node (ref "DD2") (pin "8") (pinfunction "TVDD_8") (pintype "passive"))
      (node (ref "L2") (pin "2") (pinfunction "2_2") (pintype "passive"))
      (node (ref "VT1") (pin "5") (pinfunction "G2_5") (pintype "passive"))
    )
    (net (code "86") (name "VAA") (class "Default")
      (node (ref "C51") (pin "2") (pinfunction "2_2") (pintype "passive"))
      (node (ref "C55") (pin "2") (pinfunction "2_2") (pintype "passive"))
      (node (ref "C60") (pin "2") (pinfunction "2_2") (pintype "passive"))
      (node (ref "C63") (pin "2") (pinfunction "2_2") (pintype "passive"))
      (node (ref "C64") (pin "1") (pinfunction "1_1") (pintype "passive"))
      (node (ref "DD3") (pin "25") (pinfunction "VAA_25") (pintype "power_in"))
      (node (ref "L10") (pin "2") (pinfunction "2_2") (pintype "passive"))
    )
    (net (code "87") (name "VDD_IO") (class "Default")
      (node (ref "C49") (pin "2") (pinfunction "2_2") (pintype "passive"))
      (node (ref "C53") (pin "2") (pinfunction "2_2") (pintype "passive"))
      (node (ref "C58") (pin "2") (pinfunction "2_2") (pintype "passive"))
      (node (ref "DD3") (pin "1") (pinfunction "VDD_IO_1") (pintype "power_in"))
      (node (ref "L8") (pin "2") (pinfunction "2_2") (pintype "passive"))
      (node (ref "R12") (pin "1") (pinfunction "1_1") (pintype "passive"))
    )
    (net (code "88") (name "unconnected-(DD1-PA4-Pad4)") (class "Default")
      (node (ref "DD1") (pin "4") (pinfunction "PA4_4") (pintype "passive+no_connect"))
    )
    (net (code "89") (name "unconnected-(DD1-PA5-Pad5)") (class "Default")
      (node (ref "DD1") (pin "5") (pinfunction "PA5_5") (pintype "passive+no_connect"))
    )
    (net (code "90") (name "unconnected-(DD1-PB2-Pad14)") (class "Default")
      (node (ref "DD1") (pin "14") (pinfunction "PB2_14") (pintype "passive+no_connect"))
    )
    (net (code "91") (name "unconnected-(DD1-PB3-Pad15)") (class "Default")
      (node (ref "DD1") (pin "15") (pinfunction "PB3_15") (pintype "passive+no_connect"))
    )
    (net (code "92") (name "unconnected-(DD1-PB4-Pad16)") (class "Default")
      (node (ref "DD1") (pin "16") (pinfunction "PB4_16") (pintype "passive+no_connect"))
    )
    (net (code "93") (name "unconnected-(DD1-PB5-Pad17)") (class "Default")
      (node (ref "DD1") (pin "17") (pinfunction "PB5_17") (pintype "passive+no_connect"))
    )
    (net (code "94") (name "unconnected-(DD1-PB6-Pad18)") (class "Default")
      (node (ref "DD1") (pin "18") (pinfunction "PB6_18") (pintype "passive+no_connect"))
    )
    (net (code "95") (name "unconnected-(DD1-PB7-Pad19)") (class "Default")
      (node (ref "DD1") (pin "19") (pinfunction "PB7_19") (pintype "passive+no_connect"))
    )
    (net (code "96") (name "unconnected-(DD1-PC3-Pad24)") (class "Default")
      (node (ref "DD1") (pin "24") (pinfunction "PC3_24") (pintype "passive+no_connect"))
    )
    (net (code "97") (name "unconnected-(DD1-PC5-Pad26)") (class "Default")
      (node (ref "DD1") (pin "26") (pinfunction "PC5_26") (pintype "passive+no_connect"))
    )
    (net (code "98") (name "unconnected-(DD1-PC6-Pad27)") (class "Default")
      (node (ref "DD1") (pin "27") (pinfunction "PC6_27") (pintype "passive+no_connect"))
    )
    (net (code "99") (name "unconnected-(DD1-PD0-Pad8)") (class "Default")
      (node (ref "DD1") (pin "8") (pinfunction "PD0_8") (pintype "passive+no_connect"))
    )
    (net (code "100") (name "unconnected-(DD1-PD1-Pad9)") (class "Default")
      (node (ref "DD1") (pin "9") (pinfunction "PD1_9") (pintype "passive+no_connect"))
    )
    (net (code "101") (name "unconnected-(DD1-PD2-Pad10)") (class "Default")
      (node (ref "DD1") (pin "10") (pinfunction "PD2_10") (pintype "passive+no_connect"))
    )
    (net (code "102") (name "unconnected-(DD1-PD3-Pad11)") (class "Default")
      (node (ref "DD1") (pin "11") (pinfunction "PD3_11") (pintype "passive+no_connect"))
    )
    (net (code "103") (name "unconnected-(DD1-PD4-Pad20)") (class "Default")
      (node (ref "DD1") (pin "20") (pinfunction "PD4_20") (pintype "passive+no_connect"))
    )
    (net (code "104") (name "unconnected-(DD2A-DDCA_SDA-Pad63)") (class "Default")
      (node (ref "DD2") (pin "63") (pinfunction "DDCA_SDA_63") (pintype "passive+no_connect"))
    )
    (net (code "105") (name "unconnected-(DD2A-DE-Pad45)") (class "Default")
      (node (ref "DD2") (pin "45") (pinfunction "DE_45") (pintype "passive+no_connect"))
    )
    (net (code "106") (name "unconnected-(DD2A-INT1-Pad55)") (class "Default")
      (node (ref "DD2") (pin "55") (pinfunction "INT1_55") (pintype "passive+no_connect"))
    )
    (net (code "107") (name "unconnected-(DD2A-P16-Pad22)") (class "Default")
      (node (ref "DD2") (pin "22") (pinfunction "P16_22") (pintype "passive+no_connect"))
    )
    (net (code "108") (name "unconnected-(DD2A-P17-Pad21)") (class "Default")
      (node (ref "DD2") (pin "21") (pinfunction "P17_21") (pintype "passive+no_connect"))
    )
    (net (code "109") (name "unconnected-(DD2A-P18-Pad20)") (class "Default")
      (node (ref "DD2") (pin "20") (pinfunction "P18_20") (pintype "passive+no_connect"))
    )
    (net (code "110") (name "unconnected-(DD2A-P19-Pad19)") (class "Default")
      (node (ref "DD2") (pin "19") (pinfunction "P19_19") (pintype "passive+no_connect"))
    )
    (net (code "111") (name "unconnected-(DD2A-P20-Pad18)") (class "Default")
      (node (ref "DD2") (pin "18") (pinfunction "P20_18") (pintype "passive+no_connect"))
    )
    (net (code "112") (name "unconnected-(DD2A-P21-Pad17)") (class "Default")
      (node (ref "DD2") (pin "17") (pinfunction "P21_17") (pintype "passive+no_connect"))
    )
    (net (code "113") (name "unconnected-(DD2A-P22-Pad16)") (class "Default")
      (node (ref "DD2") (pin "16") (pinfunction "P22_16") (pintype "passive+no_connect"))
    )
    (net (code "114") (name "unconnected-(DD2A-P23-Pad15)") (class "Default")
      (node (ref "DD2") (pin "15") (pinfunction "P23_15") (pintype "passive+no_connect"))
    )
    (net (code "115") (name "unconnected-(DD3A-SFL-Pad31)") (class "Default")
      (node (ref "DD3") (pin "31") (pinfunction "SFL_31") (pintype "passive+no_connect"))
    )
    (net (code "116") (name "unconnected-(DD4-CLKOUT-Pad5)") (class "Default")
      (node (ref "DD4") (pin "5") (pinfunction "CLKOUT_5") (pintype "passive+no_connect"))
    )
    (net (code "117") (name "unconnected-(DD4-LLINEIN-Pad17)") (class "Default")
      (node (ref "DD4") (pin "17") (pinfunction "LLINEIN_17") (pintype "passive+no_connect"))
    )
    (net (code "118") (name "unconnected-(DD4-NC-Pad20)") (class "Default")
      (node (ref "DD4") (pin "20") (pinfunction "NC_20") (pintype "passive+no_connect"))
    )
    (net (code "119") (name "unconnected-(DD4-RECDAT-Pad9)") (class "Default")
      (node (ref "DD4") (pin "9") (pinfunction "RECDAT_9") (pintype "passive+no_connect"))
    )
    (net (code "120") (name "unconnected-(DD4-RECLRC-Pad10)") (class "Default")
      (node (ref "DD4") (pin "10") (pinfunction "RECLRC_10") (pintype "passive+no_connect"))
    )
    (net (code "121") (name "unconnected-(DD4-RLINEIN-Pad16)") (class "Default")
      (node (ref "DD4") (pin "16") (pinfunction "RLINEIN_16") (pintype "passive+no_connect"))
    )
    (net (code "122") (name "unconnected-(DD4-XTO-Pad2)") (class "Default")
      (node (ref "DD4") (pin "2") (pinfunction "XTO_2") (pintype "passive+no_connect"))
    )
    (net (code "123") (name "unconnected-(XS2-SCL-Pad15)") (class "Default")
      (node (ref "XS2") (pin "15") (pinfunction "SCL_15") (pintype "passive+no_connect"))
    )
    (net (code "124") (name "unconnected-(XS2-SDA-Pad16)") (class "Default")
      (node (ref "XS2") (pin "16") (pinfunction "SDA_16") (pintype "passive+no_connect"))
    )
    (net (code "125") (name "unconnected-(XS2-Utility_{slash}_HEAC+-Pad17)") (class "Default")
      (node (ref "XS2") (pin "17") (pinfunction "Utility_/_HEAC+_17") (pintype "passive+no_connect"))
    )
  )
)
